# control.net
KiCad netlist of a schematic drawn in EAGLE
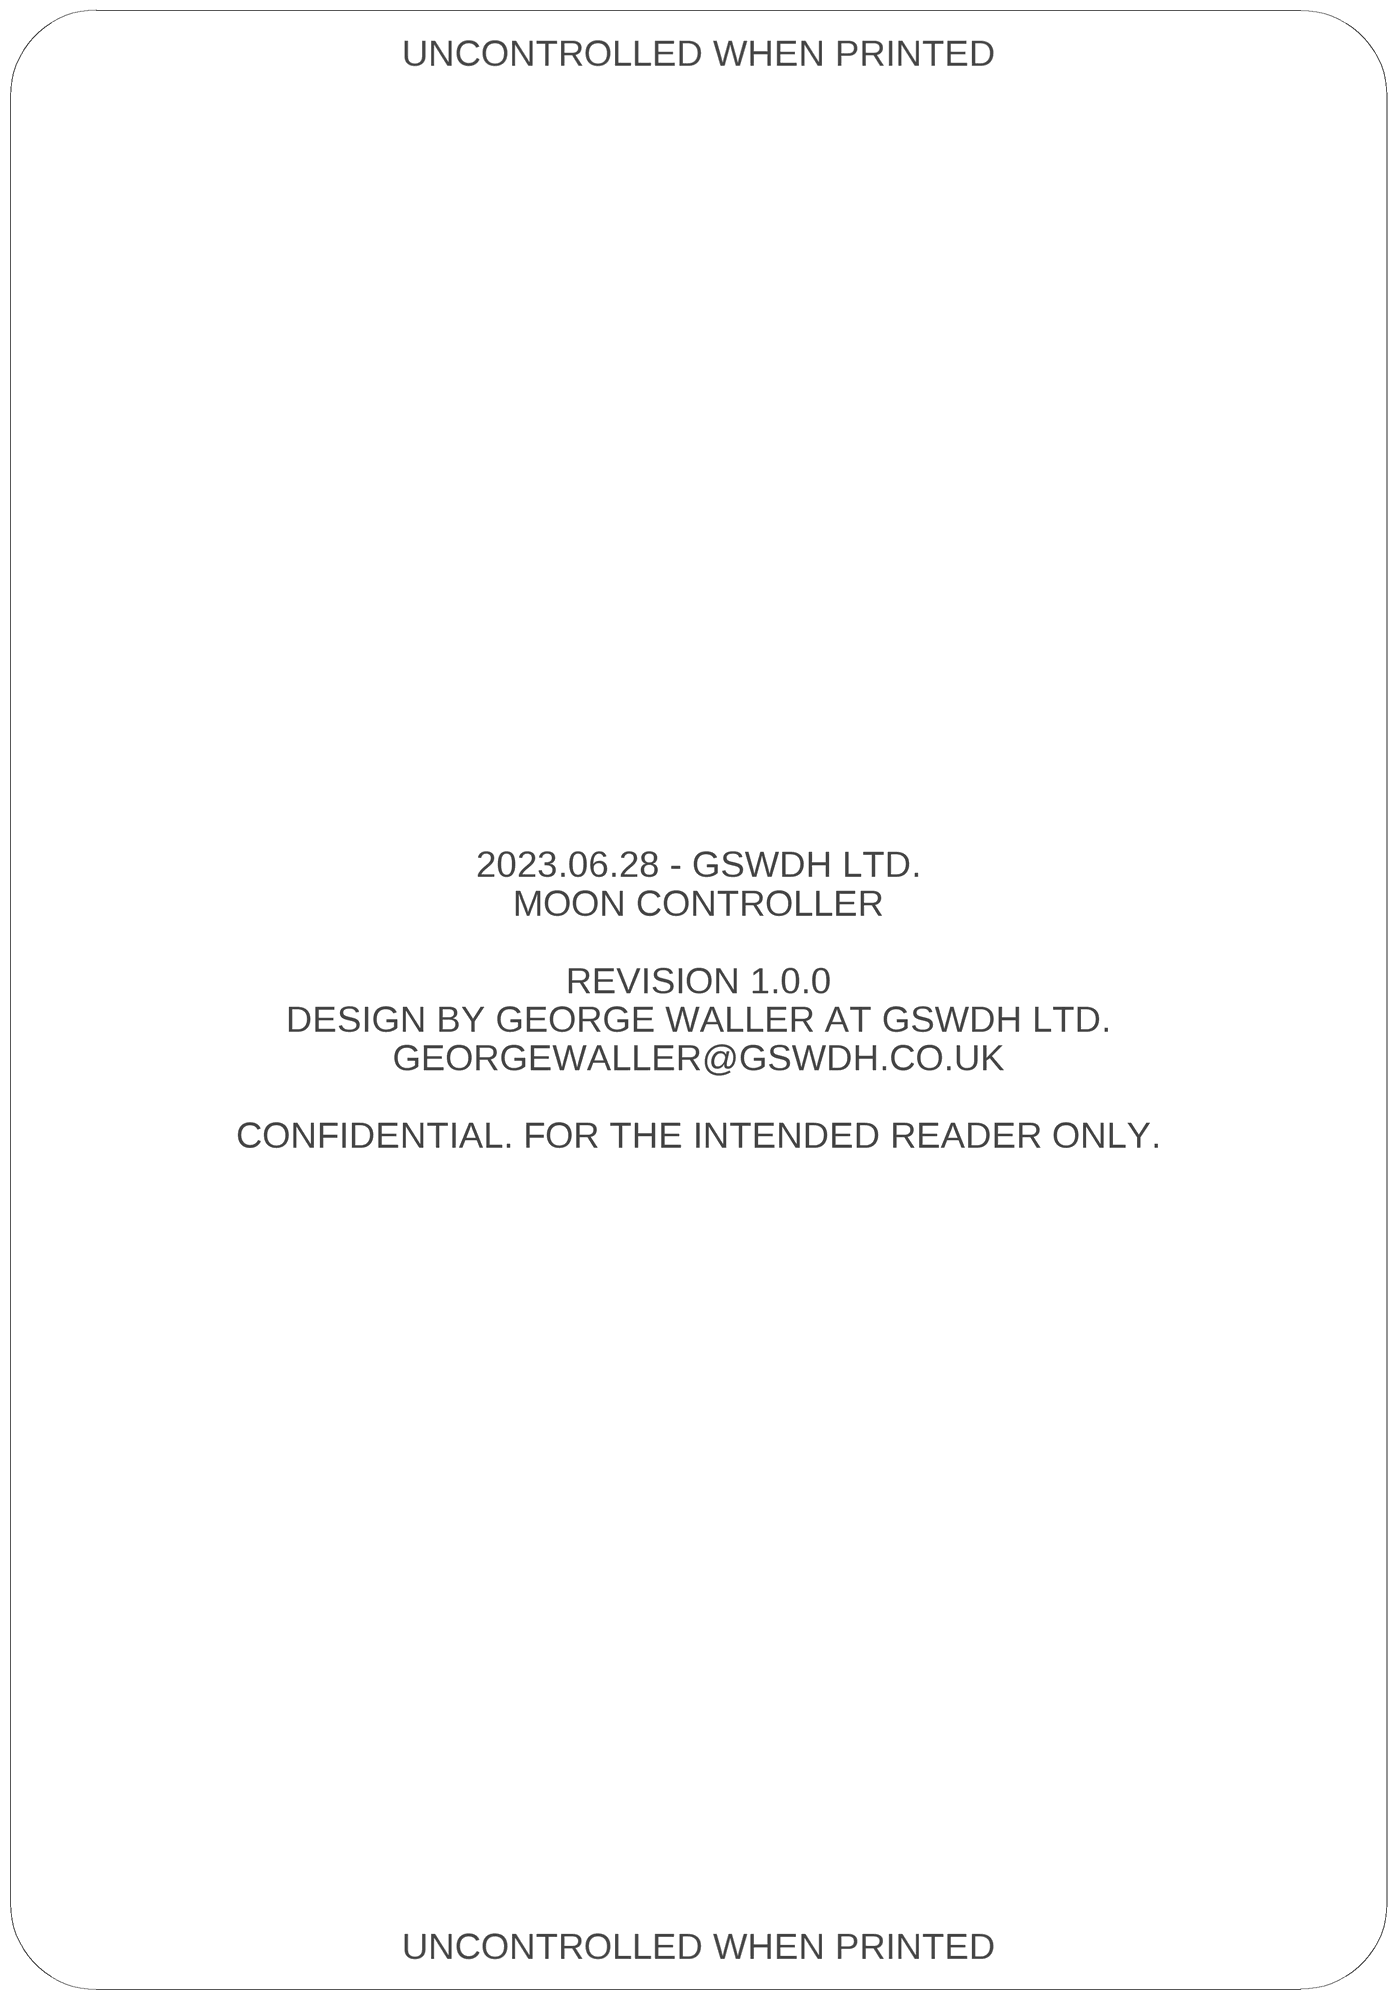
[diagram p0: schematic, sheet 1]
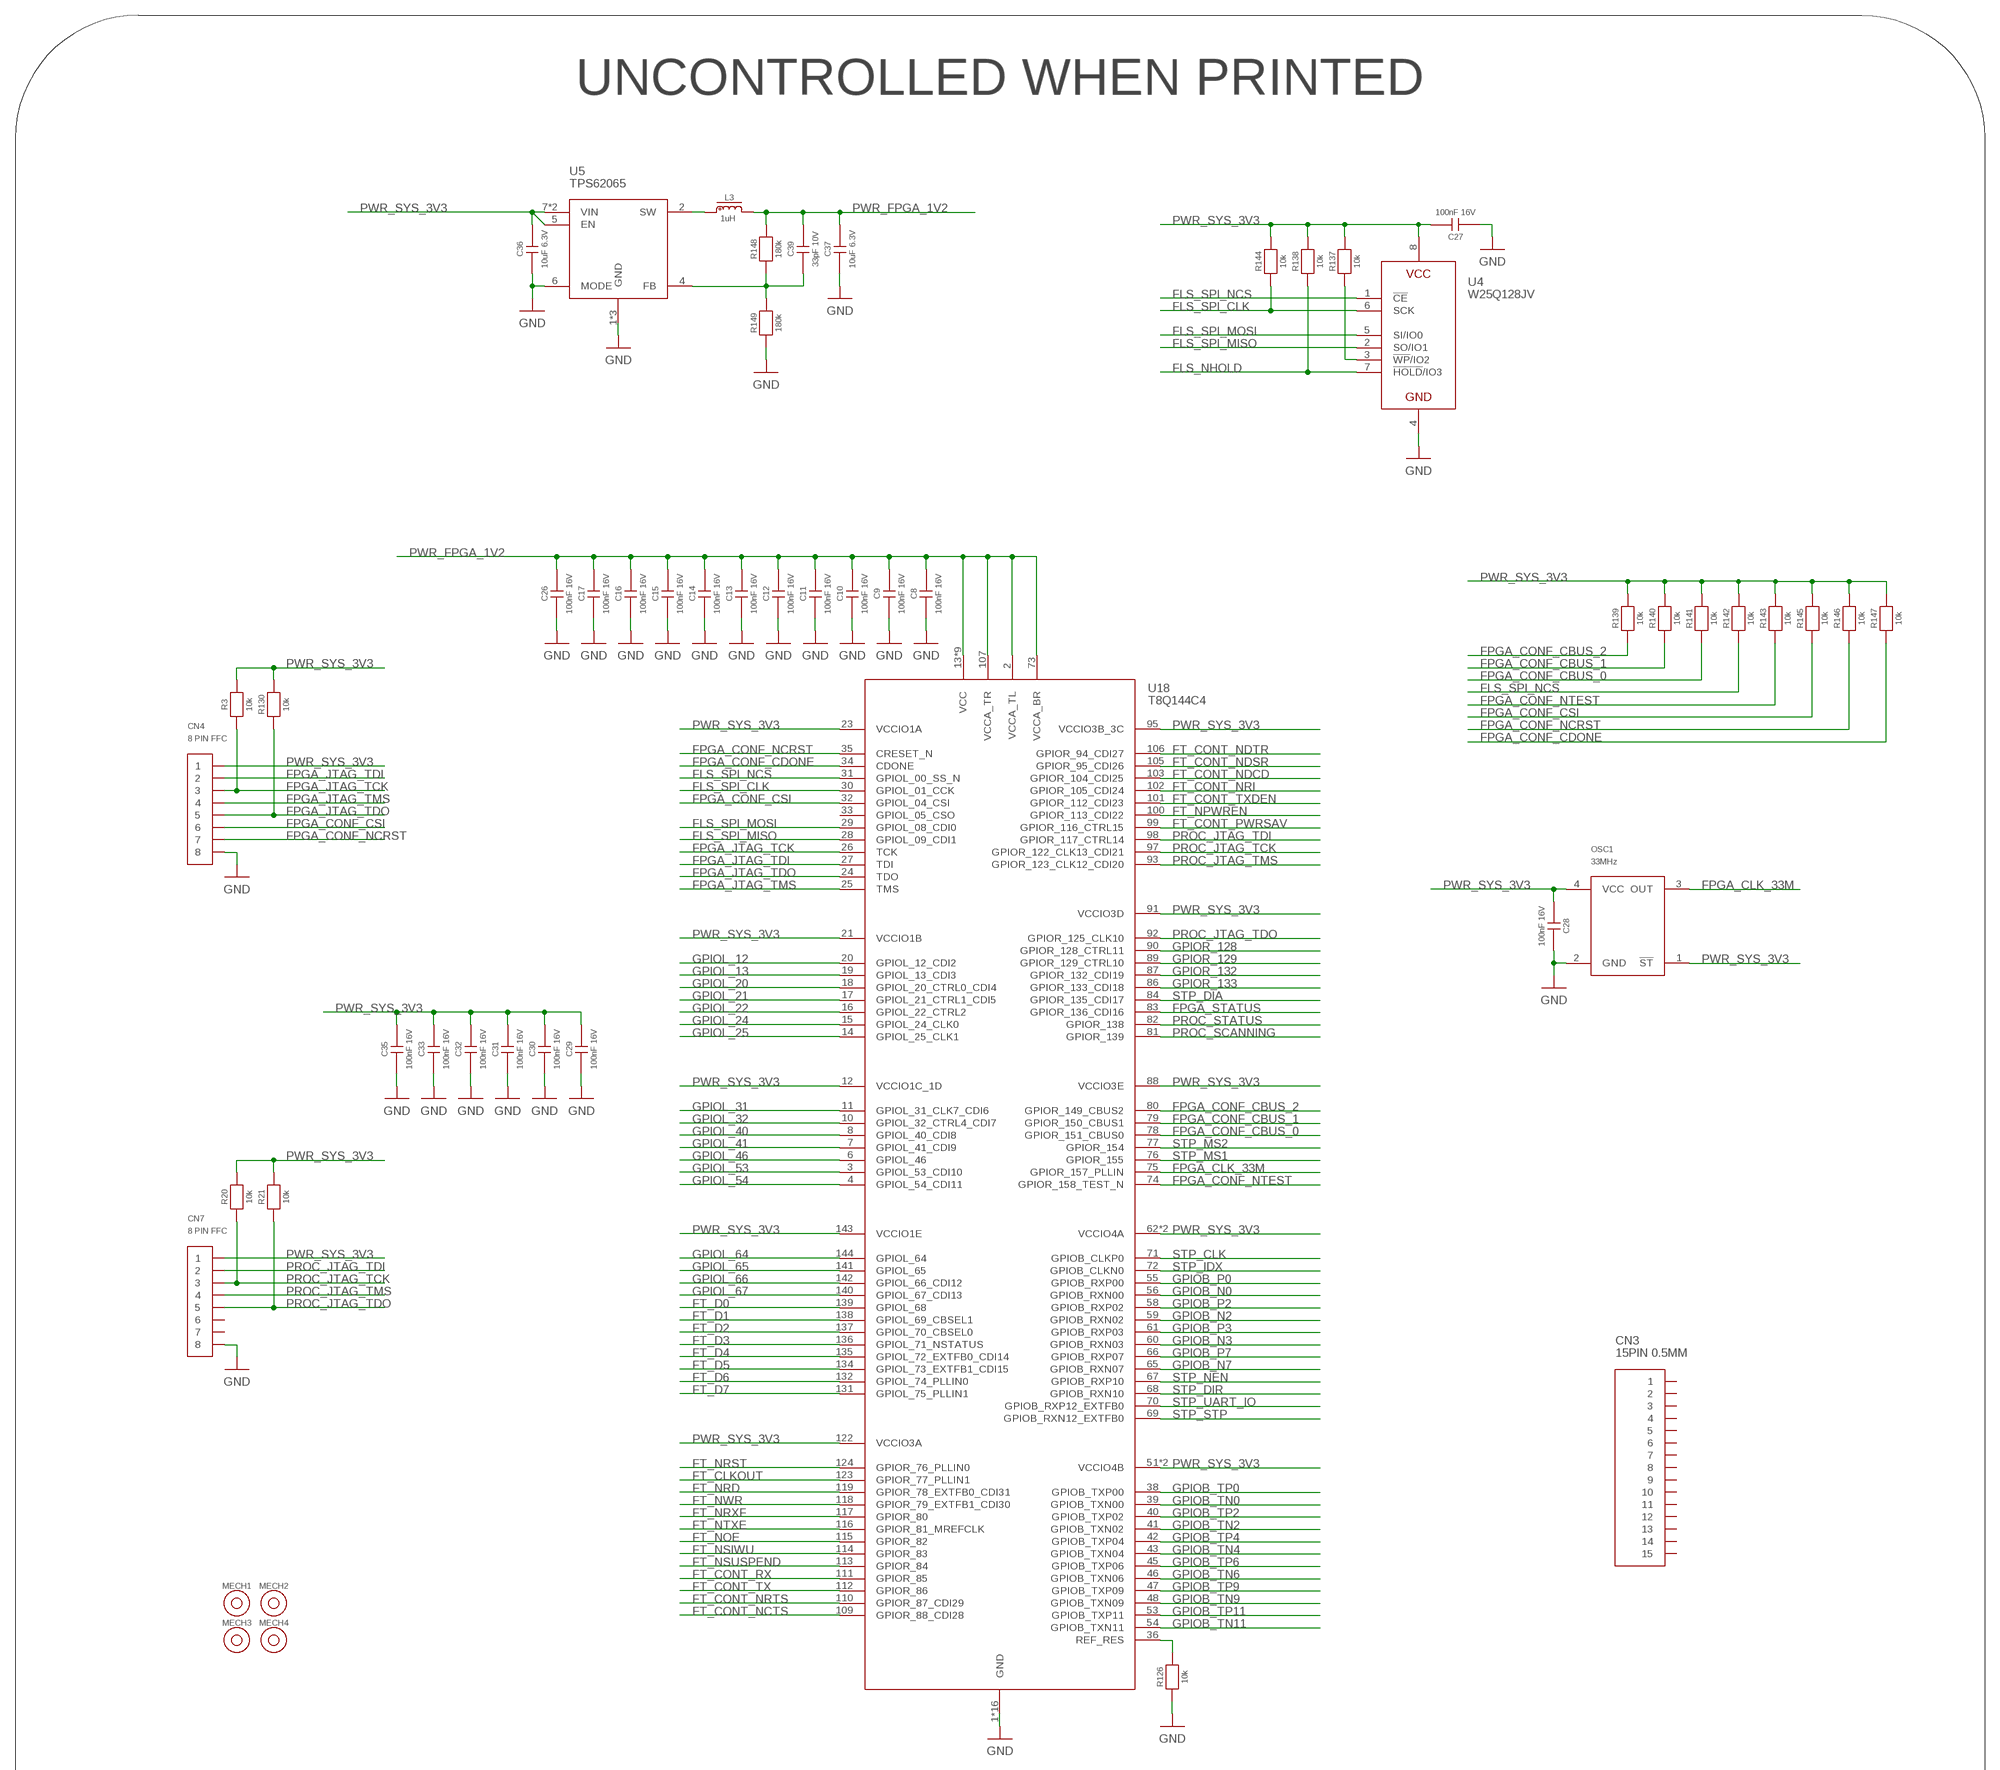
[diagram p1: schematic, sheet 2, part 1 of 2]
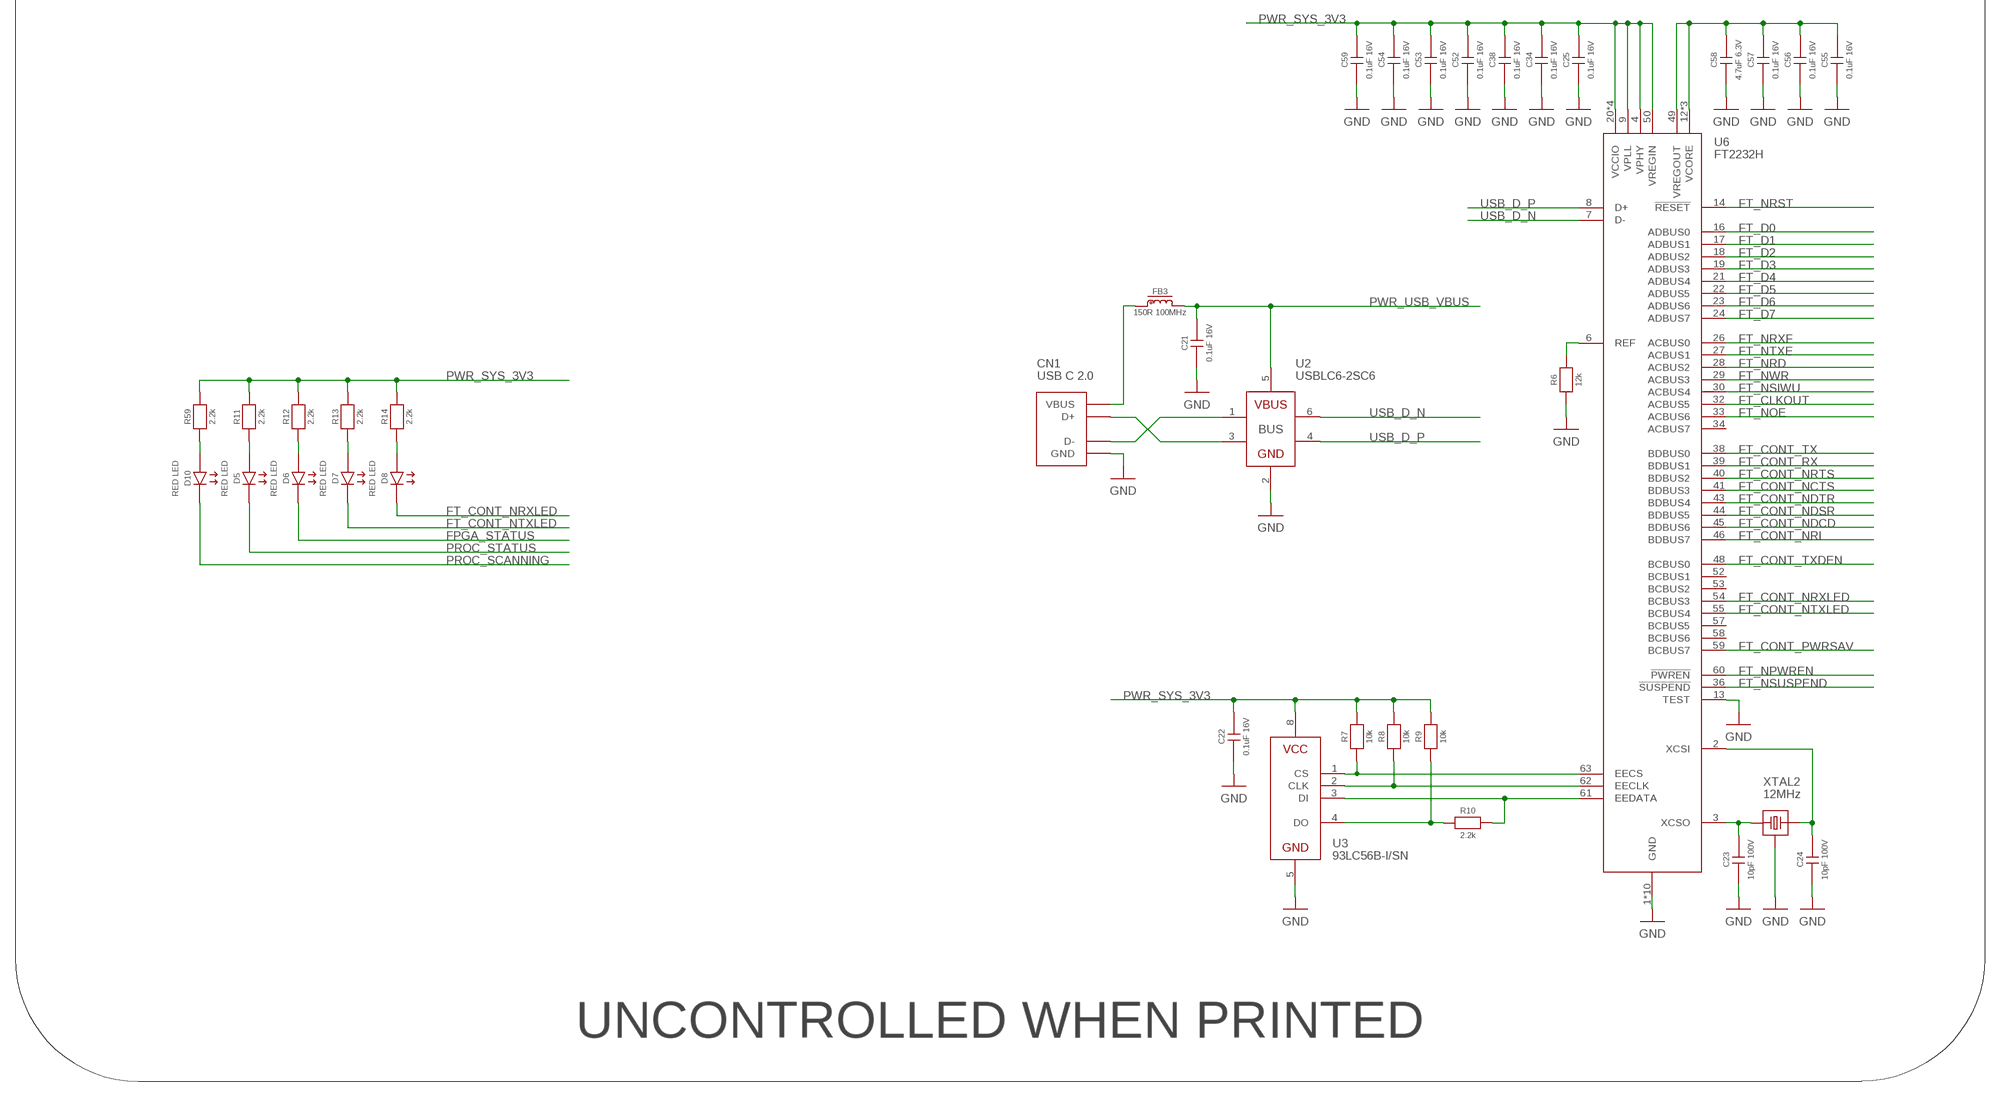
[diagram p2: schematic, sheet 2, part 2 of 2]
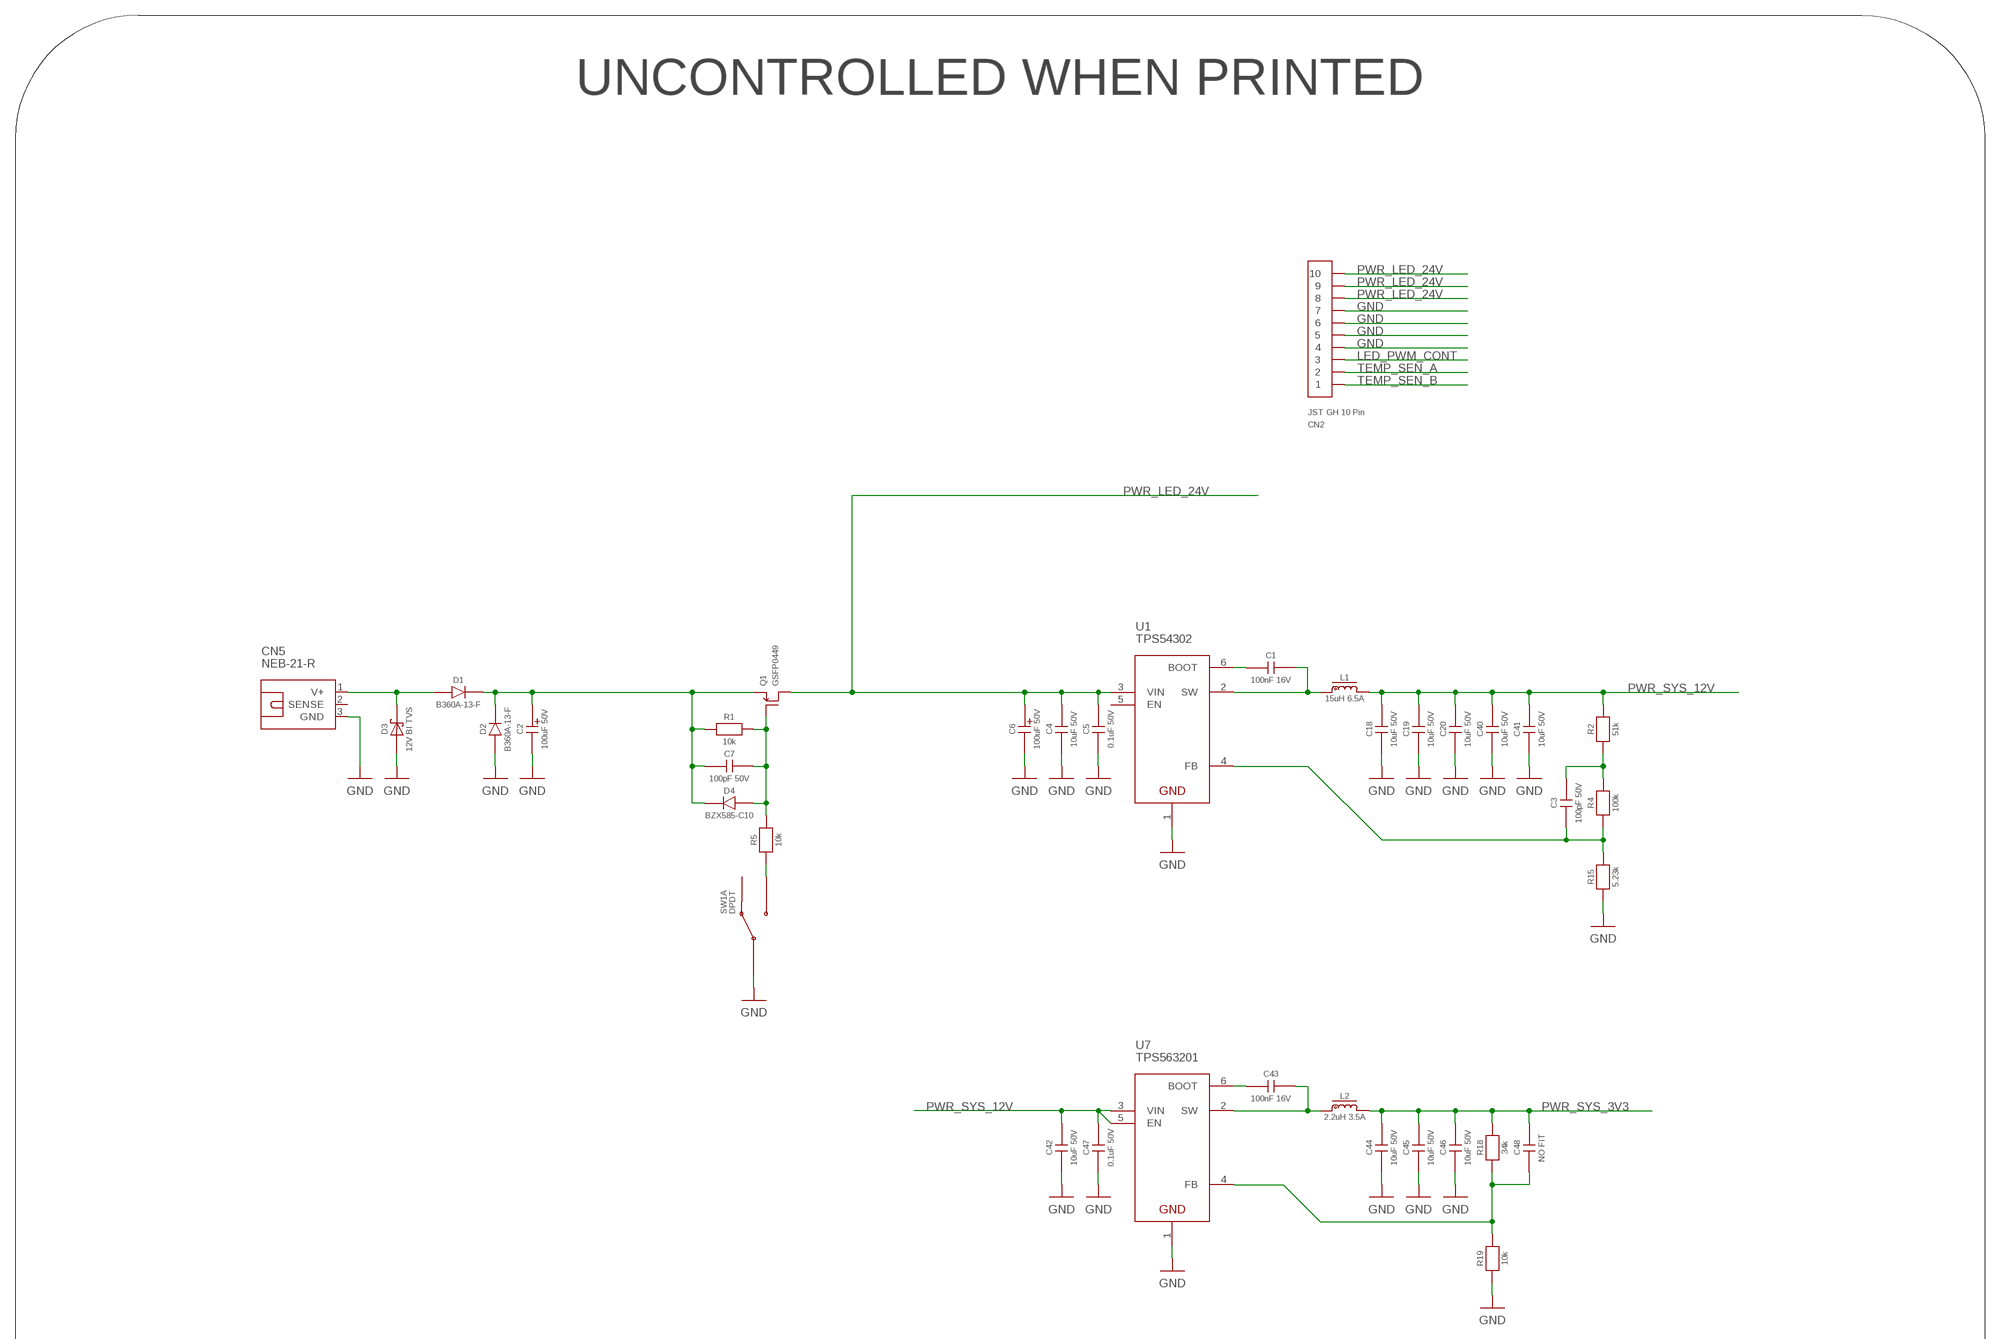
[diagram p3: schematic, sheet 3, part 1 of 2]
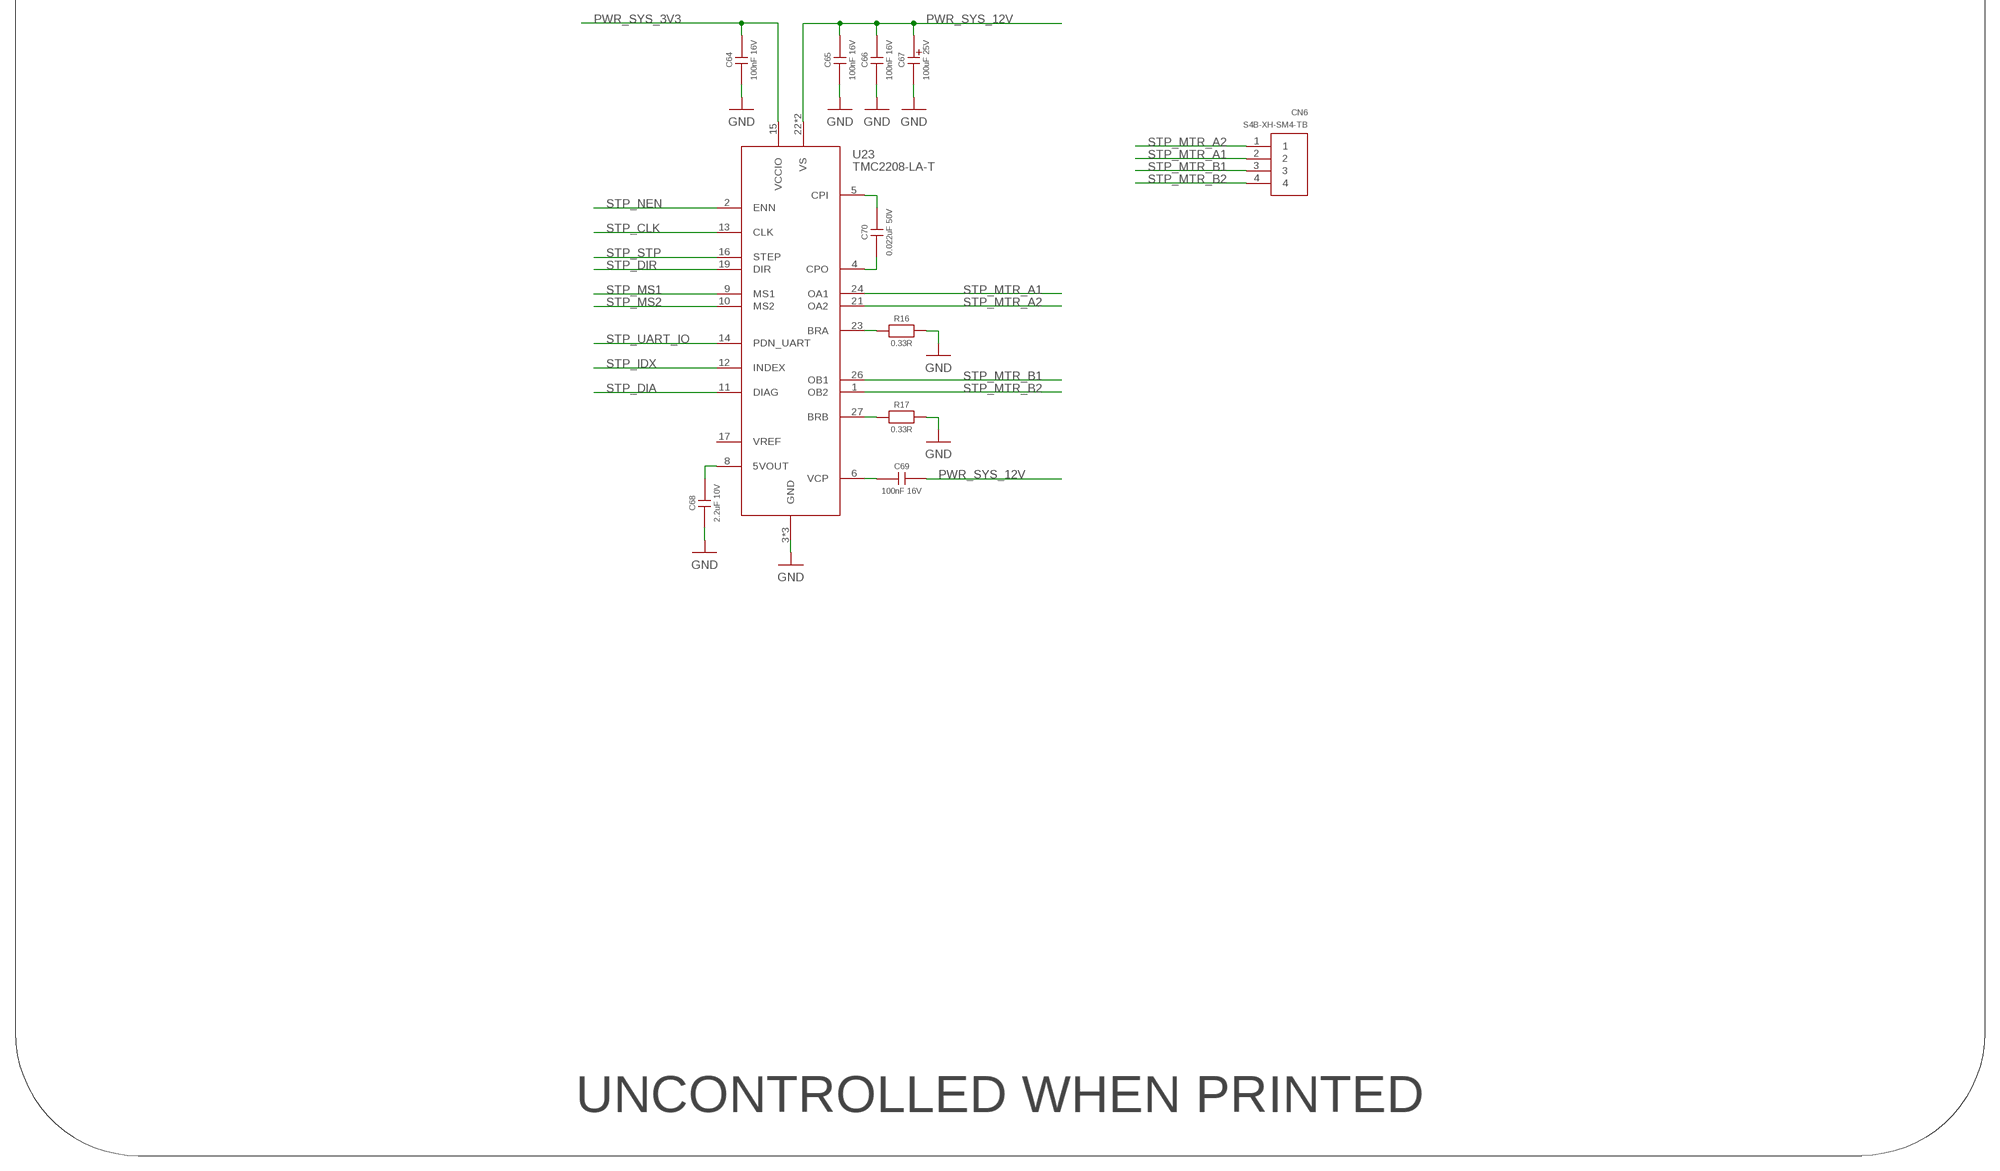
[diagram p4: schematic, sheet 3, part 2 of 2]

(export (version "E")
  (design (tool "Eeschema 10.0.6"))
  (components
    (comp (ref "C8")
      (value "100nF 16V")
      (footprint "eagle-import:0603")
      (libsource (lib "eagle-import") (part "CL10B104KO8WPNC"))
    )
    (comp (ref "C9")
      (value "100nF 16V")
      (footprint "eagle-import:0603")
      (libsource (lib "eagle-import") (part "CL10B104KO8WPNC"))
    )
    (comp (ref "C10")
      (value "100nF 16V")
      (footprint "eagle-import:0603")
      (libsource (lib "eagle-import") (part "CL10B104KO8WPNC"))
    )
    (comp (ref "C11")
      (value "100nF 16V")
      (footprint "eagle-import:0603")
      (libsource (lib "eagle-import") (part "CL10B104KO8WPNC"))
    )
    (comp (ref "C12")
      (value "100nF 16V")
      (footprint "eagle-import:0603")
      (libsource (lib "eagle-import") (part "CL10B104KO8WPNC"))
    )
    (comp (ref "C13")
      (value "100nF 16V")
      (footprint "eagle-import:0603")
      (libsource (lib "eagle-import") (part "CL10B104KO8WPNC"))
    )
    (comp (ref "C14")
      (value "100nF 16V")
      (footprint "eagle-import:0603")
      (libsource (lib "eagle-import") (part "CL10B104KO8WPNC"))
    )
    (comp (ref "C15")
      (value "100nF 16V")
      (footprint "eagle-import:0603")
      (libsource (lib "eagle-import") (part "CL10B104KO8WPNC"))
    )
    (comp (ref "C16")
      (value "100nF 16V")
      (footprint "eagle-import:0603")
      (libsource (lib "eagle-import") (part "CL10B104KO8WPNC"))
    )
    (comp (ref "C17")
      (value "100nF 16V")
      (footprint "eagle-import:0603")
      (libsource (lib "eagle-import") (part "CL10B104KO8WPNC"))
    )
    (comp (ref "C21")
      (value "0.1uF 16V")
      (footprint "eagle-import:0603")
      (fields
        (field (name "MANUFACTURER") "AVX Corporation")
        (field (name "TOLERANCE") "±5%")
        (field (name "VOLTAGE") "16V")
      )
      (libsource (lib "eagle-import") (part "0603YC104JAZ2A"))
    )
    (comp (ref "C22")
      (value "0.1uF 16V")
      (footprint "eagle-import:0603")
      (fields
        (field (name "MANUFACTURER") "AVX Corporation")
        (field (name "TOLERANCE") "±5%")
        (field (name "VOLTAGE") "16V")
      )
      (libsource (lib "eagle-import") (part "0603YC104JAZ2A"))
    )
    (comp (ref "C23")
      (value "10pF 100V")
      (footprint "eagle-import:0603")
      (fields
        (field (name "MANUFACTURER") "AVX Corporation")
        (field (name "TOLERANCE") "±0.1pF")
        (field (name "VOLTAGE") "100V")
      )
      (libsource (lib "eagle-import") (part "06031A100B4T2A"))
    )
    (comp (ref "C24")
      (value "10pF 100V")
      (footprint "eagle-import:0603")
      (fields
        (field (name "MANUFACTURER") "AVX Corporation")
        (field (name "TOLERANCE") "±0.1pF")
        (field (name "VOLTAGE") "100V")
      )
      (libsource (lib "eagle-import") (part "06031A100B4T2A"))
    )
    (comp (ref "C25")
      (value "0.1uF 16V")
      (footprint "eagle-import:0603")
      (fields
        (field (name "MANUFACTURER") "AVX Corporation")
        (field (name "TOLERANCE") "±5%")
        (field (name "VOLTAGE") "16V")
      )
      (libsource (lib "eagle-import") (part "0603YC104JAZ2A"))
    )
    (comp (ref "C26")
      (value "100nF 16V")
      (footprint "eagle-import:0603")
      (libsource (lib "eagle-import") (part "CL10B104KO8WPNC"))
    )
    (comp (ref "C27")
      (value "100nF 16V")
      (footprint "eagle-import:0603")
      (libsource (lib "eagle-import") (part "CL10B104KO8WPNC"))
    )
    (comp (ref "C28")
      (value "100nF 16V")
      (footprint "eagle-import:0603")
      (libsource (lib "eagle-import") (part "CL10B104KO8WPNC"))
    )
    (comp (ref "C29")
      (value "100nF 16V")
      (footprint "eagle-import:0603")
      (libsource (lib "eagle-import") (part "CL10B104KO8WPNC"))
    )
    (comp (ref "C30")
      (value "100nF 16V")
      (footprint "eagle-import:0603")
      (libsource (lib "eagle-import") (part "CL10B104KO8WPNC"))
    )
    (comp (ref "C31")
      (value "100nF 16V")
      (footprint "eagle-import:0603")
      (libsource (lib "eagle-import") (part "CL10B104KO8WPNC"))
    )
    (comp (ref "C32")
      (value "100nF 16V")
      (footprint "eagle-import:0603")
      (libsource (lib "eagle-import") (part "CL10B104KO8WPNC"))
    )
    (comp (ref "C33")
      (value "100nF 16V")
      (footprint "eagle-import:0603")
      (libsource (lib "eagle-import") (part "CL10B104KO8WPNC"))
    )
    (comp (ref "C34")
      (value "0.1uF 16V")
      (footprint "eagle-import:0603")
      (fields
        (field (name "MANUFACTURER") "AVX Corporation")
        (field (name "TOLERANCE") "±5%")
        (field (name "VOLTAGE") "16V")
      )
      (libsource (lib "eagle-import") (part "0603YC104JAZ2A"))
    )
    (comp (ref "C35")
      (value "100nF 16V")
      (footprint "eagle-import:0603")
      (libsource (lib "eagle-import") (part "CL10B104KO8WPNC"))
    )
    (comp (ref "C36")
      (value "10uF 6.3V")
      (footprint "eagle-import:0603")
      (fields
        (field (name "MANUFACTURER") "Samsung Electro-Mechanics")
        (field (name "TOLERANCE") "±10%")
        (field (name "VOLTAGE") "6.3V")
      )
      (libsource (lib "eagle-import") (part "CL10A106KQ8NNWC"))
    )
    (comp (ref "C37")
      (value "10uF 6.3V")
      (footprint "eagle-import:0603")
      (fields
        (field (name "MANUFACTURER") "Samsung Electro-Mechanics")
        (field (name "TOLERANCE") "±10%")
        (field (name "VOLTAGE") "6.3V")
      )
      (libsource (lib "eagle-import") (part "CL10A106KQ8NNWC"))
    )
    (comp (ref "C38")
      (value "0.1uF 16V")
      (footprint "eagle-import:0603")
      (fields
        (field (name "MANUFACTURER") "AVX Corporation")
        (field (name "TOLERANCE") "±5%")
        (field (name "VOLTAGE") "16V")
      )
      (libsource (lib "eagle-import") (part "0603YC104JAZ2A"))
    )
    (comp (ref "C39")
      (value "33pF 10V")
      (footprint "eagle-import:0603")
      (fields
        (field (name "MANUFACTURER") "KEMET")
        (field (name "TOLERANCE") "±5%")
        (field (name "VOLTAGE") "10V")
      )
      (libsource (lib "eagle-import") (part "C0603C330J8GAC7867"))
    )
    (comp (ref "C52")
      (value "0.1uF 16V")
      (footprint "eagle-import:0603")
      (fields
        (field (name "MANUFACTURER") "AVX Corporation")
        (field (name "TOLERANCE") "±5%")
        (field (name "VOLTAGE") "16V")
      )
      (libsource (lib "eagle-import") (part "0603YC104JAZ2A"))
    )
    (comp (ref "C53")
      (value "0.1uF 16V")
      (footprint "eagle-import:0603")
      (fields
        (field (name "MANUFACTURER") "AVX Corporation")
        (field (name "TOLERANCE") "±5%")
        (field (name "VOLTAGE") "16V")
      )
      (libsource (lib "eagle-import") (part "0603YC104JAZ2A"))
    )
    (comp (ref "C54")
      (value "0.1uF 16V")
      (footprint "eagle-import:0603")
      (fields
        (field (name "MANUFACTURER") "AVX Corporation")
        (field (name "TOLERANCE") "±5%")
        (field (name "VOLTAGE") "16V")
      )
      (libsource (lib "eagle-import") (part "0603YC104JAZ2A"))
    )
    (comp (ref "C55")
      (value "0.1uF 16V")
      (footprint "eagle-import:0603")
      (fields
        (field (name "MANUFACTURER") "AVX Corporation")
        (field (name "TOLERANCE") "±5%")
        (field (name "VOLTAGE") "16V")
      )
      (libsource (lib "eagle-import") (part "0603YC104JAZ2A"))
    )
    (comp (ref "C56")
      (value "0.1uF 16V")
      (footprint "eagle-import:0603")
      (fields
        (field (name "MANUFACTURER") "AVX Corporation")
        (field (name "TOLERANCE") "±5%")
        (field (name "VOLTAGE") "16V")
      )
      (libsource (lib "eagle-import") (part "0603YC104JAZ2A"))
    )
    (comp (ref "C57")
      (value "0.1uF 16V")
      (footprint "eagle-import:0603")
      (fields
        (field (name "MANUFACTURER") "AVX Corporation")
        (field (name "TOLERANCE") "±5%")
        (field (name "VOLTAGE") "16V")
      )
      (libsource (lib "eagle-import") (part "0603YC104JAZ2A"))
    )
    (comp (ref "C58")
      (value "4.7uF 6.3V")
      (footprint "eagle-import:0603")
      (fields
        (field (name "MANUFACTURER") "AVX Corporation")
        (field (name "TOLERANCE") "±10%")
        (field (name "VOLTAGE") "6.3V")
      )
      (libsource (lib "eagle-import") (part "06036D475KAT4A"))
    )
    (comp (ref "C59")
      (value "0.1uF 16V")
      (footprint "eagle-import:0603")
      (fields
        (field (name "MANUFACTURER") "AVX Corporation")
        (field (name "TOLERANCE") "±5%")
        (field (name "VOLTAGE") "16V")
      )
      (libsource (lib "eagle-import") (part "0603YC104JAZ2A"))
    )
    (comp (ref "CN1")
      (value "USB C 2.0")
      (footprint "eagle-import:MC-107D")
      (libsource (lib "eagle-import") (part "MC-107D"))
    )
    (comp (ref "CN3")
      (value "15PIN 0.5MM")
      (footprint "eagle-import:SFV15R-1STE1HLF")
      (libsource (lib "eagle-import") (part "SFV15R-1STE1HLF"))
    )
    (comp (ref "CN4")
      (value "8 PIN FFC")
      (footprint "eagle-import:SFV8R-1STBE1HLF")
      (libsource (lib "eagle-import") (part "SFV8R-1STBE1HLF"))
    )
    (comp (ref "CN7")
      (value "8 PIN FFC")
      (footprint "eagle-import:SFV8R-1STBE1HLF")
      (libsource (lib "eagle-import") (part "SFV8R-1STBE1HLF"))
    )
    (comp (ref "D5")
      (value "RED LED")
      (footprint "eagle-import:0603_POLAR")
      (libsource (lib "eagle-import") (part "150060RS75000"))
    )
    (comp (ref "D6")
      (value "RED LED")
      (footprint "eagle-import:0603_POLAR")
      (libsource (lib "eagle-import") (part "150060RS75000"))
    )
    (comp (ref "D7")
      (value "RED LED")
      (footprint "eagle-import:0603_POLAR")
      (libsource (lib "eagle-import") (part "150060RS75000"))
    )
    (comp (ref "D8")
      (value "RED LED")
      (footprint "eagle-import:0603_POLAR")
      (libsource (lib "eagle-import") (part "150060RS75000"))
    )
    (comp (ref "D10")
      (value "RED LED")
      (footprint "eagle-import:0603_POLAR")
      (libsource (lib "eagle-import") (part "150060RS75000"))
    )
    (comp (ref "FB3")
      (value "150R 100MHz")
      (footprint "eagle-import:1206")
      (libsource (lib "eagle-import") (part "ILB1206ER151V"))
    )
    (comp (ref "L3")
      (value "1uH")
      (footprint "eagle-import:1008")
      (libsource (lib "eagle-import") (part "CIGT252010EH1R0MNE"))
    )
    (comp (ref "MECH1")
      (value "6mm x 3mm")
      (footprint "eagle-import:MOUNTHOLE_6X3")
      (libsource (lib "eagle-import") (part "MOUNTHOLE"))
    )
    (comp (ref "MECH2")
      (value "6mm x 3mm")
      (footprint "eagle-import:MOUNTHOLE_6X3")
      (libsource (lib "eagle-import") (part "MOUNTHOLE"))
    )
    (comp (ref "MECH3")
      (value "6mm x 3mm")
      (footprint "eagle-import:MOUNTHOLE_6X3")
      (libsource (lib "eagle-import") (part "MOUNTHOLE"))
    )
    (comp (ref "MECH4")
      (value "6mm x 3mm")
      (footprint "eagle-import:MOUNTHOLE_6X3")
      (libsource (lib "eagle-import") (part "MOUNTHOLE"))
    )
    (comp (ref "OSC1")
      (value "33MHz")
      (footprint "eagle-import:KC2016Z")
      (libsource (lib "eagle-import") (part "KC2016Z33.0000C15XXK"))
    )
    (comp (ref "R3")
      (value "10k")
      (footprint "eagle-import:0603")
      (libsource (lib "eagle-import") (part "ERJ3EKF1002V"))
    )
    (comp (ref "R6")
      (value "12k")
      (footprint "eagle-import:0603")
      (libsource (lib "eagle-import") (part "CRCW060312K0FKEA"))
    )
    (comp (ref "R7")
      (value "10k")
      (footprint "eagle-import:0603")
      (libsource (lib "eagle-import") (part "ERJ3EKF1002V"))
    )
    (comp (ref "R8")
      (value "10k")
      (footprint "eagle-import:0603")
      (libsource (lib "eagle-import") (part "ERJ3EKF1002V"))
    )
    (comp (ref "R9")
      (value "10k")
      (footprint "eagle-import:0603")
      (libsource (lib "eagle-import") (part "ERJ3EKF1002V"))
    )
    (comp (ref "R10")
      (value "2.2k")
      (footprint "eagle-import:0603")
      (fields
        (field (name "MANUFACTURER") "Vishay Dale")
        (field (name "POWER") "0.1W, 1/10W")
        (field (name "TOLERANCE") "±1%")
      )
      (libsource (lib "eagle-import") (part "CRCW06032K20FKEA"))
    )
    (comp (ref "R11")
      (value "2.2k")
      (footprint "eagle-import:0603")
      (fields
        (field (name "MANUFACTURER") "Vishay Dale")
        (field (name "POWER") "0.1W, 1/10W")
        (field (name "TOLERANCE") "±1%")
      )
      (libsource (lib "eagle-import") (part "CRCW06032K20FKEA"))
    )
    (comp (ref "R12")
      (value "2.2k")
      (footprint "eagle-import:0603")
      (fields
        (field (name "MANUFACTURER") "Vishay Dale")
        (field (name "POWER") "0.1W, 1/10W")
        (field (name "TOLERANCE") "±1%")
      )
      (libsource (lib "eagle-import") (part "CRCW06032K20FKEA"))
    )
    (comp (ref "R13")
      (value "2.2k")
      (footprint "eagle-import:0603")
      (fields
        (field (name "MANUFACTURER") "Vishay Dale")
        (field (name "POWER") "0.1W, 1/10W")
        (field (name "TOLERANCE") "±1%")
      )
      (libsource (lib "eagle-import") (part "CRCW06032K20FKEA"))
    )
    (comp (ref "R14")
      (value "2.2k")
      (footprint "eagle-import:0603")
      (fields
        (field (name "MANUFACTURER") "Vishay Dale")
        (field (name "POWER") "0.1W, 1/10W")
        (field (name "TOLERANCE") "±1%")
      )
      (libsource (lib "eagle-import") (part "CRCW06032K20FKEA"))
    )
    (comp (ref "R20")
      (value "10k")
      (footprint "eagle-import:0603")
      (libsource (lib "eagle-import") (part "ERJ3EKF1002V"))
    )
    (comp (ref "R21")
      (value "10k")
      (footprint "eagle-import:0603")
      (libsource (lib "eagle-import") (part "ERJ3EKF1002V"))
    )
    (comp (ref "R59")
      (value "2.2k")
      (footprint "eagle-import:0603")
      (fields
        (field (name "MANUFACTURER") "Vishay Dale")
        (field (name "POWER") "0.1W, 1/10W")
        (field (name "TOLERANCE") "±1%")
      )
      (libsource (lib "eagle-import") (part "CRCW06032K20FKEA"))
    )
    (comp (ref "R126")
      (value "10k")
      (footprint "eagle-import:0603")
      (libsource (lib "eagle-import") (part "ERJ3EKF1002V"))
    )
    (comp (ref "R130")
      (value "10k")
      (footprint "eagle-import:0603")
      (libsource (lib "eagle-import") (part "ERJ3EKF1002V"))
    )
    (comp (ref "R137")
      (value "10k")
      (footprint "eagle-import:0603")
      (libsource (lib "eagle-import") (part "ERJ3EKF1002V"))
    )
    (comp (ref "R138")
      (value "10k")
      (footprint "eagle-import:0603")
      (libsource (lib "eagle-import") (part "ERJ3EKF1002V"))
    )
    (comp (ref "R139")
      (value "10k")
      (footprint "eagle-import:0603")
      (libsource (lib "eagle-import") (part "ERJ3EKF1002V"))
    )
    (comp (ref "R140")
      (value "10k")
      (footprint "eagle-import:0603")
      (libsource (lib "eagle-import") (part "ERJ3EKF1002V"))
    )
    (comp (ref "R141")
      (value "10k")
      (footprint "eagle-import:0603")
      (libsource (lib "eagle-import") (part "ERJ3EKF1002V"))
    )
    (comp (ref "R142")
      (value "10k")
      (footprint "eagle-import:0603")
      (libsource (lib "eagle-import") (part "ERJ3EKF1002V"))
    )
    (comp (ref "R143")
      (value "10k")
      (footprint "eagle-import:0603")
      (libsource (lib "eagle-import") (part "ERJ3EKF1002V"))
    )
    (comp (ref "R144")
      (value "10k")
      (footprint "eagle-import:0603")
      (libsource (lib "eagle-import") (part "ERJ3EKF1002V"))
    )
    (comp (ref "R145")
      (value "10k")
      (footprint "eagle-import:0603")
      (libsource (lib "eagle-import") (part "ERJ3EKF1002V"))
    )
    (comp (ref "R146")
      (value "10k")
      (footprint "eagle-import:0603")
      (libsource (lib "eagle-import") (part "ERJ3EKF1002V"))
    )
    (comp (ref "R147")
      (value "10k")
      (footprint "eagle-import:0603")
      (libsource (lib "eagle-import") (part "ERJ3EKF1002V"))
    )
    (comp (ref "R148")
      (value "180k")
      (footprint "eagle-import:0603")
      (fields
        (field (name "MANUFACTURER") "Vishay Dale")
        (field (name "POWER") "0.1W, 1/10W")
        (field (name "TOLERANCE") "±1%")
      )
      (libsource (lib "eagle-import") (part "CRCW0603180KFKEA"))
    )
    (comp (ref "R149")
      (value "180k")
      (footprint "eagle-import:0603")
      (fields
        (field (name "MANUFACTURER") "Vishay Dale")
        (field (name "POWER") "0.1W, 1/10W")
        (field (name "TOLERANCE") "±1%")
      )
      (libsource (lib "eagle-import") (part "CRCW0603180KFKEA"))
    )
    (comp (ref "U2")
      (value "USBLC6-2SC6")
      (footprint "eagle-import:SOT23-6")
      (libsource (lib "eagle-import") (part "USBLC6-2SC6"))
    )
    (comp (ref "U3")
      (value "93LC56B-I/SN")
      (footprint "eagle-import:SO8")
      (libsource (lib "eagle-import") (part "93LC56B-I/SN"))
    )
    (comp (ref "U4")
      (value "W25Q128JV")
      (footprint "eagle-import:SO8-208MIL")
      (libsource (lib "eagle-import") (part "W25Q128JVSIQ"))
    )
    (comp (ref "U5")
      (value "TPS62065")
      (footprint "eagle-import:WSON8")
      (libsource (lib "eagle-import") (part "TPS62065DSGR"))
    )
    (comp (ref "U6")
      (value "FT2232H")
      (footprint "eagle-import:QFN64")
      (libsource (lib "eagle-import") (part "FT2232H"))
    )
    (comp (ref "U18")
      (value "T8Q144C4")
      (footprint "eagle-import:QFP144")
      (libsource (lib "eagle-import") (part "T8Q144C4"))
    )
    (comp (ref "XTAL2")
      (value "12MHz")
      (footprint "eagle-import:3.2X3.5SMD")
      (libsource (lib "eagle-import") (part "ABM8-12.000MHZ-B2-T"))
    )
    (comp (ref "C1")
      (value "100nF 16V")
      (footprint "eagle-import:0603")
      (libsource (lib "eagle-import") (part "CL10B104KO8WPNC"))
    )
    (comp (ref "C2")
      (value "100uF 50V")
      (footprint "eagle-import:8MM_RADIAL_3.5MM_PITCH")
      (libsource (lib "eagle-import") (part "107CKR050M"))
    )
    (comp (ref "C3")
      (value "100pF 50V")
      (footprint "eagle-import:0603")
      (fields
        (field (name "MANUFACTURER") "AVX Corporation")
        (field (name "TOLERANCE") "±5%")
        (field (name "VOLTAGE") "50V")
      )
      (libsource (lib "eagle-import") (part "06035A101J4T4A"))
    )
    (comp (ref "C4")
      (value "10uF 50V")
      (footprint "eagle-import:1210")
      (libsource (lib "eagle-import") (part "C3225X7S1H106M250AB"))
    )
    (comp (ref "C5")
      (value "0.1uF 50V")
      (footprint "eagle-import:0603")
      (fields
        (field (name "MANUFACTURER") "AVX Corporation")
        (field (name "TOLERANCE") "±5%")
        (field (name "VOLTAGE") "50V")
      )
      (libsource (lib "eagle-import") (part "06035C104JAT2A"))
    )
    (comp (ref "C6")
      (value "100uF 50V")
      (footprint "eagle-import:8MM_RADIAL_3.5MM_PITCH")
      (libsource (lib "eagle-import") (part "107CKR050M"))
    )
    (comp (ref "C7")
      (value "100pF 50V")
      (footprint "eagle-import:0603")
      (fields
        (field (name "MANUFACTURER") "AVX Corporation")
        (field (name "TOLERANCE") "±5%")
        (field (name "VOLTAGE") "50V")
      )
      (libsource (lib "eagle-import") (part "06035A101J4T4A"))
    )
    (comp (ref "C18")
      (value "10uF 50V")
      (footprint "eagle-import:0805")
      (libsource (lib "eagle-import") (part "CL21A106KAYNNNE"))
    )
    (comp (ref "C19")
      (value "10uF 50V")
      (footprint "eagle-import:0805")
      (libsource (lib "eagle-import") (part "CL21A106KAYNNNE"))
    )
    (comp (ref "C20")
      (value "10uF 50V")
      (footprint "eagle-import:0805")
      (libsource (lib "eagle-import") (part "CL21A106KAYNNNE"))
    )
    (comp (ref "C40")
      (value "10uF 50V")
      (footprint "eagle-import:0805")
      (libsource (lib "eagle-import") (part "CL21A106KAYNNNE"))
    )
    (comp (ref "C41")
      (value "10uF 50V")
      (footprint "eagle-import:0805")
      (libsource (lib "eagle-import") (part "CL21A106KAYNNNE"))
    )
    (comp (ref "C42")
      (value "10uF 50V")
      (footprint "eagle-import:0805")
      (libsource (lib "eagle-import") (part "CL21A106KAYNNNE"))
    )
    (comp (ref "C43")
      (value "100nF 16V")
      (footprint "eagle-import:0603")
      (libsource (lib "eagle-import") (part "CL10B104KO8WPNC"))
    )
    (comp (ref "C44")
      (value "10uF 50V")
      (footprint "eagle-import:0805")
      (libsource (lib "eagle-import") (part "CL21A106KAYNNNE"))
    )
    (comp (ref "C45")
      (value "10uF 50V")
      (footprint "eagle-import:0805")
      (libsource (lib "eagle-import") (part "CL21A106KAYNNNE"))
    )
    (comp (ref "C46")
      (value "10uF 50V")
      (footprint "eagle-import:0805")
      (libsource (lib "eagle-import") (part "CL21A106KAYNNNE"))
    )
    (comp (ref "C47")
      (value "0.1uF 50V")
      (footprint "eagle-import:0603")
      (fields
        (field (name "MANUFACTURER") "AVX Corporation")
        (field (name "TOLERANCE") "±5%")
        (field (name "VOLTAGE") "50V")
      )
      (libsource (lib "eagle-import") (part "06035C104JAT2A"))
    )
    (comp (ref "C48")
      (value "NO FIT")
      (footprint "eagle-import:0603")
      (fields
        (field (name "MANUFACTURER") "AVX Corporation")
        (field (name "TOLERANCE") "±5%")
        (field (name "VOLTAGE") "50V")
      )
      (libsource (lib "eagle-import") (part "06035A101J4T4A"))
    )
    (comp (ref "C64")
      (value "100nF 16V")
      (footprint "eagle-import:0603")
      (libsource (lib "eagle-import") (part "CL10B104KO8WPNC"))
    )
    (comp (ref "C65")
      (value "100nF 16V")
      (footprint "eagle-import:0603")
      (libsource (lib "eagle-import") (part "CL10B104KO8WPNC"))
    )
    (comp (ref "C66")
      (value "100nF 16V")
      (footprint "eagle-import:0603")
      (libsource (lib "eagle-import") (part "CL10B104KO8WPNC"))
    )
    (comp (ref "C67")
      (value "100uF 25V")
      (footprint "eagle-import:5MM_RADIAL_2MM_PITCH")
      (libsource (lib "eagle-import") (part "UVY1E101MDD"))
    )
    (comp (ref "C68")
      (value "2.2uF 10V")
      (footprint "eagle-import:0603")
      (fields
        (field (name "MANUFACTURER") "AVX Corporation")
        (field (name "TOLERANCE") "±10%")
        (field (name "VOLTAGE") "10V")
      )
      (libsource (lib "eagle-import") (part "0603ZC225KAT2A"))
    )
    (comp (ref "C69")
      (value "100nF 16V")
      (footprint "eagle-import:0603")
      (libsource (lib "eagle-import") (part "CL10B104KO8WPNC"))
    )
    (comp (ref "C70")
      (value "0.022uF 50V")
      (footprint "eagle-import:0603")
      (fields
        (field (name "MANUFACTURER") "KEMET")
        (field (name "TOLERANCE") "±10%")
        (field (name "VOLTAGE") "50V")
      )
      (libsource (lib "eagle-import") (part "C0603C223K5REC7867"))
    )
    (comp (ref "CN2")
      (value "JST GH 10 Pin")
      (footprint "eagle-import:1.25-10PWT")
      (libsource (lib "eagle-import") (part "1.25-10PWT"))
    )
    (comp (ref "CN5")
      (value "NEB-21-R")
      (footprint "eagle-import:NEB-21-R")
      (libsource (lib "eagle-import") (part "NEB-21-R"))
    )
    (comp (ref "CN6")
      (value "S4B-XH-SM4-TB")
      (footprint "eagle-import:S4B-XH-SM4-TB")
      (libsource (lib "eagle-import") (part "S4B-XH-SM4-TB"))
    )
    (comp (ref "D1")
      (value "B360A-13-F")
      (footprint "eagle-import:DO214AC")
      (libsource (lib "eagle-import") (part "B360A-13-F"))
    )
    (comp (ref "D2")
      (value "B360A-13-F")
      (footprint "eagle-import:DO214AC")
      (libsource (lib "eagle-import") (part "B360A-13-F"))
    )
    (comp (ref "D3")
      (value "12V BI TVS")
      (footprint "eagle-import:DO214AC")
      (libsource (lib "eagle-import") (part "SMBJ12CA-13-F"))
    )
    (comp (ref "D4")
      (value "BZX585-C10")
      (footprint "eagle-import:SOD_523")
      (libsource (lib "eagle-import") (part "BZT52C10T-7"))
    )
    (comp (ref "L1")
      (value "15uH 6.5A")
      (footprint "eagle-import:SRP1035A")
      (libsource (lib "eagle-import") (part "MWSA1004S-150MT"))
    )
    (comp (ref "L2")
      (value "2.2uH 3.5A")
      (footprint "eagle-import:SRN5040")
      (libsource (lib "eagle-import") (part "SRN5040-2R2Y"))
    )
    (comp (ref "Q1")
      (value "GSFP0449")
      (footprint "eagle-import:SO8_POWERPAK")
      (libsource (lib "eagle-import") (part "GSFP0449"))
    )
    (comp (ref "R1")
      (value "10k")
      (footprint "eagle-import:0603")
      (fields
        (field (name "MANUFACTURER") "Vishay Dale")
        (field (name "POWER") "0.1W, 1/10W")
        (field (name "TOLERANCE") "±1%")
      )
      (libsource (lib "eagle-import") (part "CRCW060310K0FKTA"))
    )
    (comp (ref "R2")
      (value "51k")
      (footprint "eagle-import:0603")
      (libsource (lib "eagle-import") (part "CRCW060351K0FKEA"))
    )
    (comp (ref "R4")
      (value "100k")
      (footprint "eagle-import:0603")
      (fields
        (field (name "MANUFACTURER") "Vishay Dale")
        (field (name "POWER") "0.1W, 1/10W")
        (field (name "TOLERANCE") "±1%")
      )
      (libsource (lib "eagle-import") (part "CRCW0603100KFKEB"))
    )
    (comp (ref "R5")
      (value "10k")
      (footprint "eagle-import:0603")
      (fields
        (field (name "MANUFACTURER") "Vishay Dale")
        (field (name "POWER") "0.1W, 1/10W")
        (field (name "TOLERANCE") "±1%")
      )
      (libsource (lib "eagle-import") (part "CRCW060310K0FKTA"))
    )
    (comp (ref "R15")
      (value "5.23k")
      (footprint "eagle-import:0603")
      (fields
        (field (name "MANUFACTURER") "Vishay Dale")
        (field (name "POWER") "0.1W, 1/10W")
        (field (name "TOLERANCE") "±1%")
      )
      (libsource (lib "eagle-import") (part "CRCW06035K23FKEA"))
    )
    (comp (ref "R16")
      (value "0.33R")
      (footprint "eagle-import:0603")
      (libsource (lib "eagle-import") (part "CRL0603-FW-R330ELF"))
    )
    (comp (ref "R17")
      (value "0.33R")
      (footprint "eagle-import:0603")
      (libsource (lib "eagle-import") (part "CRL0603-FW-R330ELF"))
    )
    (comp (ref "R18")
      (value "34k")
      (footprint "eagle-import:0603")
      (fields
        (field (name "MANUFACTURER") "Vishay Dale")
        (field (name "POWER") "0.1W, 1/10W")
        (field (name "TOLERANCE") "±1%")
      )
      (libsource (lib "eagle-import") (part "CRCW060334K0FKEA"))
    )
    (comp (ref "R19")
      (value "10k")
      (footprint "eagle-import:0603")
      (fields
        (field (name "MANUFACTURER") "Vishay Dale")
        (field (name "POWER") "0.1W, 1/10W")
        (field (name "TOLERANCE") "±1%")
      )
      (libsource (lib "eagle-import") (part "CRCW060310K0FKTA"))
    )
    (comp (ref "SW1")
      (value "DPDT")
      (footprint "eagle-import:PBH2UEESNPNAGX")
      (libsource (lib "eagle-import") (part "PBH2UEESNPNAGX"))
    )
    (comp (ref "U1")
      (value "TPS54302")
      (footprint "eagle-import:SOT23-6")
      (libsource (lib "eagle-import") (part "TPS54302"))
    )
    (comp (ref "U7")
      (value "TPS563201")
      (footprint "eagle-import:SOT23-6")
      (libsource (lib "eagle-import") (part "TPS563201DDCR"))
    )
    (comp (ref "U23")
      (value "TMC2208-LA-T")
      (footprint "eagle-import:QFN28")
      (libsource (lib "eagle-import") (part "TMC2208-LA-T"))
    )
  )
  (nets
    (net (code "1") (name "FLS_NHOLD") (class "Default")
      (node (ref "R138") (pin "1") (pinfunction "1_1") (pintype "bidirectional"))
      (node (ref "U4") (pin "7") (pinfunction "~{HOLD}/IO3_7") (pintype "bidirectional"))
    )
    (net (code "2") (name "FLS_SPI_CLK") (class "Default")
      (node (ref "R144") (pin "1") (pinfunction "1_1") (pintype "bidirectional"))
      (node (ref "U18") (pin "30") (pinfunction "GPIOL_01_CCK_30") (pintype "bidirectional"))
      (node (ref "U4") (pin "6") (pinfunction "SCK_6") (pintype "bidirectional"))
    )
    (net (code "3") (name "FLS_SPI_MISO") (class "Default")
      (node (ref "U18") (pin "28") (pinfunction "GPIOL_09_CDI1_28") (pintype "bidirectional"))
      (node (ref "U4") (pin "2") (pinfunction "SO/IO1_2") (pintype "bidirectional"))
    )
    (net (code "4") (name "FLS_SPI_MOSI") (class "Default")
      (node (ref "U18") (pin "29") (pinfunction "GPIOL_08_CDI0_29") (pintype "bidirectional"))
      (node (ref "U4") (pin "5") (pinfunction "SI/IO0_5") (pintype "bidirectional"))
    )
    (net (code "5") (name "FLS_SPI_NCS") (class "Default")
      (node (ref "R142") (pin "1") (pinfunction "1_1") (pintype "bidirectional"))
      (node (ref "U18") (pin "31") (pinfunction "GPIOL_00_SS_N_31") (pintype "bidirectional"))
      (node (ref "U4") (pin "1") (pinfunction "~{CE}_1") (pintype "bidirectional"))
    )
    (net (code "6") (name "FPGA_CLK_33M") (class "Default")
      (node (ref "OSC1") (pin "3") (pinfunction "OUT_3") (pintype "bidirectional"))
      (node (ref "U18") (pin "75") (pinfunction "GPIOR_157_PLLIN_75") (pintype "bidirectional"))
    )
    (net (code "7") (name "FPGA_CONF_CBUS_0") (class "Default")
      (node (ref "R141") (pin "1") (pinfunction "1_1") (pintype "bidirectional"))
      (node (ref "U18") (pin "78") (pinfunction "GPIOR_151_CBUS0_78") (pintype "bidirectional"))
    )
    (net (code "8") (name "FPGA_CONF_CBUS_1") (class "Default")
      (node (ref "R140") (pin "1") (pinfunction "1_1") (pintype "bidirectional"))
      (node (ref "U18") (pin "79") (pinfunction "GPIOR_150_CBUS1_79") (pintype "bidirectional"))
    )
    (net (code "9") (name "FPGA_CONF_CBUS_2") (class "Default")
      (node (ref "R139") (pin "1") (pinfunction "1_1") (pintype "bidirectional"))
      (node (ref "U18") (pin "80") (pinfunction "GPIOR_149_CBUS2_80") (pintype "bidirectional"))
    )
    (net (code "10") (name "FPGA_CONF_CDONE") (class "Default")
      (node (ref "R147") (pin "1") (pinfunction "1_1") (pintype "bidirectional"))
      (node (ref "U18") (pin "34") (pinfunction "CDONE_34") (pintype "bidirectional"))
    )
    (net (code "11") (name "FPGA_CONF_CSI") (class "Default")
      (node (ref "CN4") (pin "6") (pinfunction "6_6") (pintype "bidirectional"))
      (node (ref "R145") (pin "1") (pinfunction "1_1") (pintype "bidirectional"))
      (node (ref "U18") (pin "32") (pinfunction "GPIOL_04_CSI_32") (pintype "bidirectional"))
    )
    (net (code "12") (name "FPGA_CONF_NCRST") (class "Default")
      (node (ref "CN4") (pin "7") (pinfunction "7_7") (pintype "bidirectional"))
      (node (ref "R146") (pin "1") (pinfunction "1_1") (pintype "bidirectional"))
      (node (ref "U18") (pin "35") (pinfunction "CRESET_N_35") (pintype "bidirectional"))
    )
    (net (code "13") (name "FPGA_CONF_NTEST") (class "Default")
      (node (ref "R143") (pin "1") (pinfunction "1_1") (pintype "bidirectional"))
      (node (ref "U18") (pin "74") (pinfunction "GPIOR_158_TEST_N_74") (pintype "bidirectional"))
    )
    (net (code "14") (name "FPGA_JTAG_TCK") (class "Default")
      (node (ref "CN4") (pin "3") (pinfunction "3_3") (pintype "bidirectional"))
      (node (ref "R3") (pin "1") (pinfunction "1_1") (pintype "bidirectional"))
      (node (ref "U18") (pin "26") (pinfunction "TCK_26") (pintype "bidirectional"))
    )
    (net (code "15") (name "FPGA_JTAG_TDI") (class "Default")
      (node (ref "CN4") (pin "2") (pinfunction "2_2") (pintype "bidirectional"))
      (node (ref "U18") (pin "27") (pinfunction "TDI_27") (pintype "bidirectional"))
    )
    (net (code "16") (name "FPGA_JTAG_TDO") (class "Default")
      (node (ref "CN4") (pin "5") (pinfunction "5_5") (pintype "bidirectional"))
      (node (ref "R130") (pin "1") (pinfunction "1_1") (pintype "bidirectional"))
      (node (ref "U18") (pin "24") (pinfunction "TDO_24") (pintype "bidirectional"))
    )
    (net (code "17") (name "FPGA_JTAG_TMS") (class "Default")
      (node (ref "CN4") (pin "4") (pinfunction "4_4") (pintype "bidirectional"))
      (node (ref "U18") (pin "25") (pinfunction "TMS_25") (pintype "bidirectional"))
    )
    (net (code "18") (name "FPGA_STATUS") (class "Default")
      (node (ref "D6") (pin "K") (pinfunction "K_K") (pintype "bidirectional"))
      (node (ref "U18") (pin "83") (pinfunction "GPIOR_136_CDI16_83") (pintype "bidirectional"))
    )
    (net (code "19") (name "FT_CLKOUT") (class "Default")
      (node (ref "U18") (pin "123") (pinfunction "GPIOR_77_PLLIN1_123") (pintype "bidirectional"))
      (node (ref "U6") (pin "32") (pinfunction "ACBUS5_32") (pintype "bidirectional"))
    )
    (net (code "20") (name "FT_CONT_NCTS") (class "Default")
      (node (ref "U18") (pin "109") (pinfunction "GPIOR_88_CDI28_109") (pintype "bidirectional"))
      (node (ref "U6") (pin "41") (pinfunction "BDBUS3_41") (pintype "bidirectional"))
    )
    (net (code "21") (name "FT_CONT_NDCD") (class "Default")
      (node (ref "U18") (pin "103") (pinfunction "GPIOR_104_CDI25_103") (pintype "bidirectional"))
      (node (ref "U6") (pin "45") (pinfunction "BDBUS6_45") (pintype "bidirectional"))
    )
    (net (code "22") (name "FT_CONT_NDSR") (class "Default")
      (node (ref "U18") (pin "105") (pinfunction "GPIOR_95_CDI26_105") (pintype "bidirectional"))
      (node (ref "U6") (pin "44") (pinfunction "BDBUS5_44") (pintype "bidirectional"))
    )
    (net (code "23") (name "FT_CONT_NDTR") (class "Default")
      (node (ref "U18") (pin "106") (pinfunction "GPIOR_94_CDI27_106") (pintype "bidirectional"))
      (node (ref "U6") (pin "43") (pinfunction "BDBUS4_43") (pintype "bidirectional"))
    )
    (net (code "24") (name "FT_CONT_NRI") (class "Default")
      (node (ref "U18") (pin "102") (pinfunction "GPIOR_105_CDI24_102") (pintype "bidirectional"))
      (node (ref "U6") (pin "46") (pinfunction "BDBUS7_46") (pintype "bidirectional"))
    )
    (net (code "25") (name "FT_CONT_NRTS") (class "Default")
      (node (ref "U18") (pin "110") (pinfunction "GPIOR_87_CDI29_110") (pintype "bidirectional"))
      (node (ref "U6") (pin "40") (pinfunction "BDBUS2_40") (pintype "bidirectional"))
    )
    (net (code "26") (name "FT_CONT_NRXLED") (class "Default")
      (node (ref "D8") (pin "K") (pinfunction "K_K") (pintype "bidirectional"))
      (node (ref "U6") (pin "54") (pinfunction "BCBUS3_54") (pintype "bidirectional"))
    )
    (net (code "27") (name "FT_CONT_NTXLED") (class "Default")
      (node (ref "D7") (pin "K") (pinfunction "K_K") (pintype "bidirectional"))
      (node (ref "U6") (pin "55") (pinfunction "BCBUS4_55") (pintype "bidirectional"))
    )
    (net (code "28") (name "FT_CONT_PWRSAV") (class "Default")
      (node (ref "U18") (pin "99") (pinfunction "GPIOR_116_CTRL15_99") (pintype "bidirectional"))
      (node (ref "U6") (pin "59") (pinfunction "BCBUS7_59") (pintype "bidirectional"))
    )
    (net (code "29") (name "FT_CONT_RX") (class "Default")
      (node (ref "U18") (pin "111") (pinfunction "GPIOR_85_111") (pintype "bidirectional"))
      (node (ref "U6") (pin "39") (pinfunction "BDBUS1_39") (pintype "bidirectional"))
    )
    (net (code "30") (name "FT_CONT_TX") (class "Default")
      (node (ref "U18") (pin "112") (pinfunction "GPIOR_86_112") (pintype "bidirectional"))
      (node (ref "U6") (pin "38") (pinfunction "BDBUS0_38") (pintype "bidirectional"))
    )
    (net (code "31") (name "FT_CONT_TXDEN") (class "Default")
      (node (ref "U18") (pin "101") (pinfunction "GPIOR_112_CDI23_101") (pintype "bidirectional"))
      (node (ref "U6") (pin "48") (pinfunction "BCBUS0_48") (pintype "bidirectional"))
    )
    (net (code "32") (name "FT_D0") (class "Default")
      (node (ref "U18") (pin "139") (pinfunction "GPIOL_68_139") (pintype "bidirectional"))
      (node (ref "U6") (pin "16") (pinfunction "ADBUS0_16") (pintype "bidirectional"))
    )
    (net (code "33") (name "FT_D1") (class "Default")
      (node (ref "U18") (pin "138") (pinfunction "GPIOL_69_CBSEL1_138") (pintype "bidirectional"))
      (node (ref "U6") (pin "17") (pinfunction "ADBUS1_17") (pintype "bidirectional"))
    )
    (net (code "34") (name "FT_D2") (class "Default")
      (node (ref "U18") (pin "137") (pinfunction "GPIOL_70_CBSEL0_137") (pintype "bidirectional"))
      (node (ref "U6") (pin "18") (pinfunction "ADBUS2_18") (pintype "bidirectional"))
    )
    (net (code "35") (name "FT_D3") (class "Default")
      (node (ref "U18") (pin "136") (pinfunction "GPIOL_71_NSTATUS_136") (pintype "bidirectional"))
      (node (ref "U6") (pin "19") (pinfunction "ADBUS3_19") (pintype "bidirectional"))
    )
    (net (code "36") (name "FT_D4") (class "Default")
      (node (ref "U18") (pin "135") (pinfunction "GPIOL_72_EXTFB0_CDI14_135") (pintype "bidirectional"))
      (node (ref "U6") (pin "21") (pinfunction "ADBUS4_21") (pintype "bidirectional"))
    )
    (net (code "37") (name "FT_D5") (class "Default")
      (node (ref "U18") (pin "134") (pinfunction "GPIOL_73_EXTFB1_CDI15_134") (pintype "bidirectional"))
      (node (ref "U6") (pin "22") (pinfunction "ADBUS5_22") (pintype "bidirectional"))
    )
    (net (code "38") (name "FT_D6") (class "Default")
      (node (ref "U18") (pin "132") (pinfunction "GPIOL_74_PLLIN0_132") (pintype "bidirectional"))
      (node (ref "U6") (pin "23") (pinfunction "ADBUS6_23") (pintype "bidirectional"))
    )
    (net (code "39") (name "FT_D7") (class "Default")
      (node (ref "U18") (pin "131") (pinfunction "GPIOL_75_PLLIN1_131") (pintype "bidirectional"))
      (node (ref "U6") (pin "24") (pinfunction "ADBUS7_24") (pintype "bidirectional"))
    )
    (net (code "40") (name "FT_NOE") (class "Default")
      (node (ref "U18") (pin "115") (pinfunction "GPIOR_82_115") (pintype "bidirectional"))
      (node (ref "U6") (pin "33") (pinfunction "ACBUS6_33") (pintype "bidirectional"))
    )
    (net (code "41") (name "FT_NPWREN") (class "Default")
      (node (ref "U18") (pin "100") (pinfunction "GPIOR_113_CDI22_100") (pintype "bidirectional"))
      (node (ref "U6") (pin "60") (pinfunction "~{PWREN}_60") (pintype "bidirectional"))
    )
    (net (code "42") (name "FT_NRD") (class "Default")
      (node (ref "U18") (pin "119") (pinfunction "GPIOR_78_EXTFB0_CDI31_119") (pintype "bidirectional"))
      (node (ref "U6") (pin "28") (pinfunction "ACBUS2_28") (pintype "bidirectional"))
    )
    (net (code "43") (name "FT_NRST") (class "Default")
      (node (ref "U18") (pin "124") (pinfunction "GPIOR_76_PLLIN0_124") (pintype "bidirectional"))
      (node (ref "U6") (pin "14") (pinfunction "~{RESET}_14") (pintype "bidirectional"))
    )
    (net (code "44") (name "FT_NRXF") (class "Default")
      (node (ref "U18") (pin "117") (pinfunction "GPIOR_80_117") (pintype "bidirectional"))
      (node (ref "U6") (pin "26") (pinfunction "ACBUS0_26") (pintype "bidirectional"))
    )
    (net (code "45") (name "FT_NSIWU") (class "Default")
      (node (ref "U18") (pin "114") (pinfunction "GPIOR_83_114") (pintype "bidirectional"))
      (node (ref "U6") (pin "30") (pinfunction "ACBUS4_30") (pintype "bidirectional"))
    )
    (net (code "46") (name "FT_NSUSPEND") (class "Default")
      (node (ref "U18") (pin "113") (pinfunction "GPIOR_84_113") (pintype "bidirectional"))
      (node (ref "U6") (pin "36") (pinfunction "~{SUSPEND}_36") (pintype "bidirectional"))
    )
    (net (code "47") (name "FT_NTXE") (class "Default")
      (node (ref "U18") (pin "116") (pinfunction "GPIOR_81_MREFCLK_116") (pintype "bidirectional"))
      (node (ref "U6") (pin "27") (pinfunction "ACBUS1_27") (pintype "bidirectional"))
    )
    (net (code "48") (name "FT_NWR") (class "Default")
      (node (ref "U18") (pin "118") (pinfunction "GPIOR_79_EXTFB1_CDI30_118") (pintype "bidirectional"))
      (node (ref "U6") (pin "29") (pinfunction "ACBUS3_29") (pintype "bidirectional"))
    )
    (net (code "49") (name "GND") (class "Default")
      (node (ref "C10") (pin "1") (pinfunction "1_1") (pintype "bidirectional"))
      (node (ref "C11") (pin "1") (pinfunction "1_1") (pintype "bidirectional"))
      (node (ref "C12") (pin "1") (pinfunction "1_1") (pintype "bidirectional"))
      (node (ref "C13") (pin "1") (pinfunction "1_1") (pintype "bidirectional"))
      (node (ref "C14") (pin "1") (pinfunction "1_1") (pintype "bidirectional"))
      (node (ref "C15") (pin "1") (pinfunction "1_1") (pintype "bidirectional"))
      (node (ref "C16") (pin "1") (pinfunction "1_1") (pintype "bidirectional"))
      (node (ref "C17") (pin "1") (pinfunction "1_1") (pintype "bidirectional"))
      (node (ref "C18") (pin "1") (pinfunction "1_1") (pintype "bidirectional"))
      (node (ref "C19") (pin "1") (pinfunction "1_1") (pintype "bidirectional"))
      (node (ref "C2") (pin "N") (pinfunction "K_N") (pintype "bidirectional"))
      (node (ref "C20") (pin "1") (pinfunction "1_1") (pintype "bidirectional"))
      (node (ref "C21") (pin "1") (pinfunction "1_1") (pintype "bidirectional"))
      (node (ref "C22") (pin "1") (pinfunction "1_1") (pintype "bidirectional"))
      (node (ref "C23") (pin "1") (pinfunction "1_1") (pintype "bidirectional"))
      (node (ref "C24") (pin "1") (pinfunction "1_1") (pintype "bidirectional"))
      (node (ref "C25") (pin "1") (pinfunction "1_1") (pintype "bidirectional"))
      (node (ref "C26") (pin "1") (pinfunction "1_1") (pintype "bidirectional"))
      (node (ref "C27") (pin "1") (pinfunction "1_1") (pintype "bidirectional"))
      (node (ref "C28") (pin "2") (pinfunction "2_2") (pintype "bidirectional"))
      (node (ref "C29") (pin "1") (pinfunction "1_1") (pintype "bidirectional"))
      (node (ref "C30") (pin "1") (pinfunction "1_1") (pintype "bidirectional"))
      (node (ref "C31") (pin "1") (pinfunction "1_1") (pintype "bidirectional"))
      (node (ref "C32") (pin "1") (pinfunction "1_1") (pintype "bidirectional"))
      (node (ref "C33") (pin "1") (pinfunction "1_1") (pintype "bidirectional"))
      (node (ref "C34") (pin "1") (pinfunction "1_1") (pintype "bidirectional"))
      (node (ref "C35") (pin "1") (pinfunction "1_1") (pintype "bidirectional"))
      (node (ref "C36") (pin "1") (pinfunction "1_1") (pintype "bidirectional"))
      (node (ref "C37") (pin "1") (pinfunction "1_1") (pintype "bidirectional"))
      (node (ref "C38") (pin "1") (pinfunction "1_1") (pintype "bidirectional"))
      (node (ref "C4") (pin "1") (pinfunction "1_1") (pintype "bidirectional"))
      (node (ref "C40") (pin "1") (pinfunction "1_1") (pintype "bidirectional"))
      (node (ref "C41") (pin "1") (pinfunction "1_1") (pintype "bidirectional"))
      (node (ref "C42") (pin "1") (pinfunction "1_1") (pintype "bidirectional"))
      (node (ref "C44") (pin "1") (pinfunction "1_1") (pintype "bidirectional"))
      (node (ref "C45") (pin "1") (pinfunction "1_1") (pintype "bidirectional"))
      (node (ref "C46") (pin "1") (pinfunction "1_1") (pintype "bidirectional"))
      (node (ref "C47") (pin "1") (pinfunction "1_1") (pintype "bidirectional"))
      (node (ref "C5") (pin "1") (pinfunction "1_1") (pintype "bidirectional"))
      (node (ref "C52") (pin "1") (pinfunction "1_1") (pintype "bidirectional"))
      (node (ref "C53") (pin "1") (pinfunction "1_1") (pintype "bidirectional"))
      (node (ref "C54") (pin "1") (pinfunction "1_1") (pintype "bidirectional"))
      (node (ref "C55") (pin "1") (pinfunction "1_1") (pintype "bidirectional"))
      (node (ref "C56") (pin "1") (pinfunction "1_1") (pintype "bidirectional"))
      (node (ref "C57") (pin "1") (pinfunction "1_1") (pintype "bidirectional"))
      (node (ref "C58") (pin "1") (pinfunction "1_1") (pintype "bidirectional"))
      (node (ref "C59") (pin "1") (pinfunction "1_1") (pintype "bidirectional"))
      (node (ref "C6") (pin "N") (pinfunction "K_N") (pintype "bidirectional"))
      (node (ref "C64") (pin "1") (pinfunction "1_1") (pintype "bidirectional"))
      (node (ref "C65") (pin "1") (pinfunction "1_1") (pintype "bidirectional"))
      (node (ref "C66") (pin "1") (pinfunction "1_1") (pintype "bidirectional"))
      (node (ref "C67") (pin "2") (pinfunction "K_2") (pintype "bidirectional"))
      (node (ref "C68") (pin "1") (pinfunction "1_1") (pintype "bidirectional"))
      (node (ref "C8") (pin "1") (pinfunction "1_1") (pintype "bidirectional"))
      (node (ref "C9") (pin "1") (pinfunction "1_1") (pintype "bidirectional"))
      (node (ref "CN1") (pin "A12B1") (pinfunction "GND_A12B1") (pintype "bidirectional"))
      (node (ref "CN1") (pin "B12A1") (pinfunction "GND_B12A1") (pintype "bidirectional"))
      (node (ref "CN1") (pin "P$1") (pinfunction "GND_P$1") (pintype "bidirectional"))
      (node (ref "CN1") (pin "P$10") (pinfunction "GND_P$10") (pintype "bidirectional"))
      (node (ref "CN1") (pin "P$11") (pinfunction "GND_P$11") (pintype "bidirectional"))
      (node (ref "CN1") (pin "P$12") (pinfunction "GND_P$12") (pintype "bidirectional"))
      (node (ref "CN1") (pin "P$13") (pinfunction "GND_P$13") (pintype "bidirectional"))
      (node (ref "CN1") (pin "P$14") (pinfunction "GND_P$14") (pintype "bidirectional"))
      (node (ref "CN1") (pin "P$15") (pinfunction "GND_P$15") (pintype "bidirectional"))
      (node (ref "CN1") (pin "P$16") (pinfunction "GND_P$16") (pintype "bidirectional"))
      (node (ref "CN1") (pin "P$17") (pinfunction "GND_P$17") (pintype "bidirectional"))
      (node (ref "CN1") (pin "P$18") (pinfunction "GND_P$18") (pintype "bidirectional"))
      (node (ref "CN1") (pin "P$19") (pinfunction "GND_P$19") (pintype "bidirectional"))
      (node (ref "CN1") (pin "P$2") (pinfunction "GND_P$2") (pintype "bidirectional"))
      (node (ref "CN1") (pin "P$20") (pinfunction "GND_P$20") (pintype "bidirectional"))
      (node (ref "CN1") (pin "P$21") (pinfunction "GND_P$21") (pintype "bidirectional"))
      (node (ref "CN1") (pin "P$22") (pinfunction "GND_P$22") (pintype "bidirectional"))
      (node (ref "CN1") (pin "P$23") (pinfunction "GND_P$23") (pintype "bidirectional"))
      (node (ref "CN1") (pin "P$24") (pinfunction "GND_P$24") (pintype "bidirectional"))
      (node (ref "CN1") (pin "P$3") (pinfunction "GND_P$3") (pintype "bidirectional"))
      (node (ref "CN1") (pin "P$4") (pinfunction "GND_P$4") (pintype "bidirectional"))
      (node (ref "CN1") (pin "P$5") (pinfunction "GND_P$5") (pintype "bidirectional"))
      (node (ref "CN1") (pin "P$6") (pinfunction "GND_P$6") (pintype "bidirectional"))
      (node (ref "CN1") (pin "P$7") (pinfunction "GND_P$7") (pintype "bidirectional"))
      (node (ref "CN1") (pin "P$8") (pinfunction "GND_P$8") (pintype "bidirectional"))
      (node (ref "CN1") (pin "P$9") (pinfunction "GND_P$9") (pintype "bidirectional"))
      (node (ref "CN2") (pin "4") (pinfunction "4_4") (pintype "bidirectional"))
      (node (ref "CN2") (pin "5") (pinfunction "5_5") (pintype "bidirectional"))
      (node (ref "CN2") (pin "6") (pinfunction "6_6") (pintype "bidirectional"))
      (node (ref "CN2") (pin "7") (pinfunction "7_7") (pintype "bidirectional"))
      (node (ref "CN4") (pin "8") (pinfunction "8_8") (pintype "bidirectional"))
      (node (ref "CN5") (pin "3") (pinfunction "GND_3") (pintype "bidirectional"))
      (node (ref "CN7") (pin "8") (pinfunction "8_8") (pintype "bidirectional"))
      (node (ref "D2") (pin "A") (pinfunction "A_A") (pintype "bidirectional"))
      (node (ref "D3") (pin "A") (pinfunction "A_A") (pintype "bidirectional"))
      (node (ref "OSC1") (pin "2") (pinfunction "GND_2") (pintype "bidirectional"))
      (node (ref "R126") (pin "1") (pinfunction "1_1") (pintype "bidirectional"))
      (node (ref "R149") (pin "1") (pinfunction "1_1") (pintype "bidirectional"))
      (node (ref "R15") (pin "1") (pinfunction "1_1") (pintype "bidirectional"))
      (node (ref "R16") (pin "2") (pinfunction "2_2") (pintype "bidirectional"))
      (node (ref "R17") (pin "2") (pinfunction "2_2") (pintype "bidirectional"))
      (node (ref "R19") (pin "1") (pinfunction "1_1") (pintype "bidirectional"))
      (node (ref "R6") (pin "1") (pinfunction "1_1") (pintype "bidirectional"))
      (node (ref "SW1") (pin "2") (pinfunction "1_2") (pintype "bidirectional"))
      (node (ref "U1") (pin "1") (pinfunction "GND_1") (pintype "bidirectional"))
      (node (ref "U18") (pin "1") (pinfunction "GND_1") (pintype "bidirectional"))
      (node (ref "U18") (pin "104") (pinfunction "GND_104") (pintype "bidirectional"))
      (node (ref "U18") (pin "108") (pinfunction "GND_108") (pintype "bidirectional"))
      (node (ref "U18") (pin "120") (pinfunction "GND_120") (pintype "bidirectional"))
      (node (ref "U18") (pin "121") (pinfunction "GND_121") (pintype "bidirectional"))
      (node (ref "U18") (pin "126") (pinfunction "GND_126") (pintype "bidirectional"))
      (node (ref "U18") (pin "127") (pinfunction "GND_127") (pintype "bidirectional"))
      (node (ref "U18") (pin "129") (pinfunction "GND_129") (pintype "bidirectional"))
      (node (ref "U18") (pin "133") (pinfunction "GND_133") (pintype "bidirectional"))
      (node (ref "U18") (pin "37") (pinfunction "GND_37") (pintype "bidirectional"))
      (node (ref "U18") (pin "44") (pinfunction "GND_44") (pintype "bidirectional"))
      (node (ref "U18") (pin "5") (pinfunction "GND_5") (pintype "bidirectional"))
      (node (ref "U18") (pin "50") (pinfunction "GND_50") (pintype "bidirectional"))
      (node (ref "U18") (pin "64") (pinfunction "GND_64") (pintype "bidirectional"))
      (node (ref "U18") (pin "9") (pinfunction "GND_9") (pintype "bidirectional"))
      (node (ref "U18") (pin "94") (pinfunction "GND_94") (pintype "bidirectional"))
      (node (ref "U2") (pin "2") (pinfunction "GND_2") (pintype "bidirectional"))
      (node (ref "U23") (pin "18") (pinfunction "GND_18") (pintype "bidirectional"))
      (node (ref "U23") (pin "29") (pinfunction "GND_29") (pintype "bidirectional"))
      (node (ref "U23") (pin "3") (pinfunction "GND_3") (pintype "bidirectional"))
      (node (ref "U3") (pin "5") (pinfunction "GND_5") (pintype "bidirectional"))
      (node (ref "U4") (pin "4") (pinfunction "GND_4") (pintype "bidirectional"))
      (node (ref "U5") (pin "1") (pinfunction "GND_1") (pintype "bidirectional"))
      (node (ref "U5") (pin "3") (pinfunction "GND_3") (pintype "bidirectional"))
      (node (ref "U5") (pin "6") (pinfunction "MODE_6") (pintype "bidirectional"))
      (node (ref "U5") (pin "PAD") (pinfunction "GND_PAD") (pintype "bidirectional"))
      (node (ref "U6") (pin "1") (pinfunction "GND_1") (pintype "bidirectional"))
      (node (ref "U6") (pin "10") (pinfunction "GND_10") (pintype "bidirectional"))
      (node (ref "U6") (pin "11") (pinfunction "GND_11") (pintype "bidirectional"))
      (node (ref "U6") (pin "13") (pinfunction "TEST_13") (pintype "bidirectional"))
      (node (ref "U6") (pin "15") (pinfunction "GND_15") (pintype "bidirectional"))
      (node (ref "U6") (pin "25") (pinfunction "GND_25") (pintype "bidirectional"))
      (node (ref "U6") (pin "35") (pinfunction "GND_35") (pintype "bidirectional"))
      (node (ref "U6") (pin "47") (pinfunction "GND_47") (pintype "bidirectional"))
      (node (ref "U6") (pin "5") (pinfunction "GND_5") (pintype "bidirectional"))
      (node (ref "U6") (pin "51") (pinfunction "GND_51") (pintype "bidirectional"))
      (node (ref "U6") (pin "PAD") (pinfunction "GND_PAD") (pintype "bidirectional"))
      (node (ref "U7") (pin "1") (pinfunction "GND_1") (pintype "bidirectional"))
      (node (ref "XTAL2") (pin "2") (pinfunction "GND_2") (pintype "bidirectional"))
      (node (ref "XTAL2") (pin "4") (pinfunction "GND_4") (pintype "bidirectional"))
    )
    (net (code "50") (name "GPIOB_N0") (class "Default")
      (node (ref "U18") (pin "56") (pinfunction "GPIOB_RXN00_56") (pintype "bidirectional"))
    )
    (net (code "51") (name "GPIOB_N2") (class "Default")
      (node (ref "U18") (pin "59") (pinfunction "GPIOB_RXN02_59") (pintype "bidirectional"))
    )
    (net (code "52") (name "GPIOB_N3") (class "Default")
      (node (ref "U18") (pin "60") (pinfunction "GPIOB_RXN03_60") (pintype "bidirectional"))
    )
    (net (code "53") (name "GPIOB_N7") (class "Default")
      (node (ref "U18") (pin "65") (pinfunction "GPIOB_RXN07_65") (pintype "bidirectional"))
    )
    (net (code "54") (name "GPIOB_P0") (class "Default")
      (node (ref "U18") (pin "55") (pinfunction "GPIOB_RXP00_55") (pintype "bidirectional"))
    )
    (net (code "55") (name "GPIOB_P2") (class "Default")
      (node (ref "U18") (pin "58") (pinfunction "GPIOB_RXP02_58") (pintype "bidirectional"))
    )
    (net (code "56") (name "GPIOB_P3") (class "Default")
      (node (ref "U18") (pin "61") (pinfunction "GPIOB_RXP03_61") (pintype "bidirectional"))
    )
    (net (code "57") (name "GPIOB_P7") (class "Default")
      (node (ref "U18") (pin "66") (pinfunction "GPIOB_RXP07_66") (pintype "bidirectional"))
    )
    (net (code "58") (name "GPIOB_TN0") (class "Default")
      (node (ref "U18") (pin "39") (pinfunction "GPIOB_TXN00_39") (pintype "bidirectional"))
    )
    (net (code "59") (name "GPIOB_TN2") (class "Default")
      (node (ref "U18") (pin "41") (pinfunction "GPIOB_TXN02_41") (pintype "bidirectional"))
    )
    (net (code "60") (name "GPIOB_TN4") (class "Default")
      (node (ref "U18") (pin "43") (pinfunction "GPIOB_TXN04_43") (pintype "bidirectional"))
    )
    (net (code "61") (name "GPIOB_TN6") (class "Default")
      (node (ref "U18") (pin "46") (pinfunction "GPIOB_TXN06_46") (pintype "bidirectional"))
    )
    (net (code "62") (name "GPIOB_TN9") (class "Default")
      (node (ref "U18") (pin "48") (pinfunction "GPIOB_TXN09_48") (pintype "bidirectional"))
    )
    (net (code "63") (name "GPIOB_TN11") (class "Default")
      (node (ref "U18") (pin "54") (pinfunction "GPIOB_TXN11_54") (pintype "bidirectional"))
    )
    (net (code "64") (name "GPIOB_TP0") (class "Default")
      (node (ref "U18") (pin "38") (pinfunction "GPIOB_TXP00_38") (pintype "bidirectional"))
    )
    (net (code "65") (name "GPIOB_TP2") (class "Default")
      (node (ref "U18") (pin "40") (pinfunction "GPIOB_TXP02_40") (pintype "bidirectional"))
    )
    (net (code "66") (name "GPIOB_TP4") (class "Default")
      (node (ref "U18") (pin "42") (pinfunction "GPIOB_TXP04_42") (pintype "bidirectional"))
    )
    (net (code "67") (name "GPIOB_TP6") (class "Default")
      (node (ref "U18") (pin "45") (pinfunction "GPIOB_TXP06_45") (pintype "bidirectional"))
    )
    (net (code "68") (name "GPIOB_TP9") (class "Default")
      (node (ref "U18") (pin "47") (pinfunction "GPIOB_TXP09_47") (pintype "bidirectional"))
    )
    (net (code "69") (name "GPIOB_TP11") (class "Default")
      (node (ref "U18") (pin "53") (pinfunction "GPIOB_TXP11_53") (pintype "bidirectional"))
    )
    (net (code "70") (name "GPIOL_12") (class "Default")
      (node (ref "U18") (pin "20") (pinfunction "GPIOL_12_CDI2_20") (pintype "bidirectional"))
    )
    (net (code "71") (name "GPIOL_13") (class "Default")
      (node (ref "U18") (pin "19") (pinfunction "GPIOL_13_CDI3_19") (pintype "bidirectional"))
    )
    (net (code "72") (name "GPIOL_20") (class "Default")
      (node (ref "U18") (pin "18") (pinfunction "GPIOL_20_CTRL0_CDI4_18") (pintype "bidirectional"))
    )
    (net (code "73") (name "GPIOL_21") (class "Default")
      (node (ref "U18") (pin "17") (pinfunction "GPIOL_21_CTRL1_CDI5_17") (pintype "bidirectional"))
    )
    (net (code "74") (name "GPIOL_22") (class "Default")
      (node (ref "U18") (pin "16") (pinfunction "GPIOL_22_CTRL2_16") (pintype "bidirectional"))
    )
    (net (code "75") (name "GPIOL_24") (class "Default")
      (node (ref "U18") (pin "15") (pinfunction "GPIOL_24_CLK0_15") (pintype "bidirectional"))
    )
    (net (code "76") (name "GPIOL_25") (class "Default")
      (node (ref "U18") (pin "14") (pinfunction "GPIOL_25_CLK1_14") (pintype "bidirectional"))
    )
    (net (code "77") (name "GPIOL_31") (class "Default")
      (node (ref "U18") (pin "11") (pinfunction "GPIOL_31_CLK7_CDI6_11") (pintype "bidirectional"))
    )
    (net (code "78") (name "GPIOL_32") (class "Default")
      (node (ref "U18") (pin "10") (pinfunction "GPIOL_32_CTRL4_CDI7_10") (pintype "bidirectional"))
    )
    (net (code "79") (name "GPIOL_40") (class "Default")
      (node (ref "U18") (pin "8") (pinfunction "GPIOL_40_CDI8_8") (pintype "bidirectional"))
    )
    (net (code "80") (name "GPIOL_41") (class "Default")
      (node (ref "U18") (pin "7") (pinfunction "GPIOL_41_CDI9_7") (pintype "bidirectional"))
    )
    (net (code "81") (name "GPIOL_46") (class "Default")
      (node (ref "U18") (pin "6") (pinfunction "GPIOL_46_6") (pintype "bidirectional"))
    )
    (net (code "82") (name "GPIOL_53") (class "Default")
      (node (ref "U18") (pin "3") (pinfunction "GPIOL_53_CDI10_3") (pintype "bidirectional"))
    )
    (net (code "83") (name "GPIOL_54") (class "Default")
      (node (ref "U18") (pin "4") (pinfunction "GPIOL_54_CDI11_4") (pintype "bidirectional"))
    )
    (net (code "84") (name "GPIOL_64") (class "Default")
      (node (ref "U18") (pin "144") (pinfunction "GPIOL_64_144") (pintype "bidirectional"))
    )
    (net (code "85") (name "GPIOL_65") (class "Default")
      (node (ref "U18") (pin "141") (pinfunction "GPIOL_65_141") (pintype "bidirectional"))
    )
    (net (code "86") (name "GPIOL_66") (class "Default")
      (node (ref "U18") (pin "142") (pinfunction "GPIOL_66_CDI12_142") (pintype "bidirectional"))
    )
    (net (code "87") (name "GPIOL_67") (class "Default")
      (node (ref "U18") (pin "140") (pinfunction "GPIOL_67_CDI13_140") (pintype "bidirectional"))
    )
    (net (code "88") (name "GPIOR_128") (class "Default")
      (node (ref "U18") (pin "90") (pinfunction "GPIOR_128_CTRL11_90") (pintype "bidirectional"))
    )
    (net (code "89") (name "GPIOR_129") (class "Default")
      (node (ref "U18") (pin "89") (pinfunction "GPIOR_129_CTRL10_89") (pintype "bidirectional"))
    )
    (net (code "90") (name "GPIOR_132") (class "Default")
      (node (ref "U18") (pin "87") (pinfunction "GPIOR_132_CDI19_87") (pintype "bidirectional"))
    )
    (net (code "91") (name "GPIOR_133") (class "Default")
      (node (ref "U18") (pin "86") (pinfunction "GPIOR_133_CDI18_86") (pintype "bidirectional"))
    )
    (net (code "92") (name "LED_PWM_CONT") (class "Default")
      (node (ref "CN2") (pin "3") (pinfunction "3_3") (pintype "bidirectional"))
    )
    (net (code "93") (name "Net-(C2-A)") (class "Default")
      (node (ref "C2") (pin "P") (pinfunction "A_P") (pintype "bidirectional"))
      (node (ref "C7") (pin "1") (pinfunction "1_1") (pintype "bidirectional"))
      (node (ref "D1") (pin "K") (pinfunction "K_K") (pintype "bidirectional"))
      (node (ref "D2") (pin "K") (pinfunction "K_K") (pintype "bidirectional"))
      (node (ref "D4") (pin "K") (pinfunction "K_K") (pintype "bidirectional"))
      (node (ref "Q1") (pin "1") (pinfunction "S_1") (pintype "bidirectional"))
      (node (ref "Q1") (pin "2") (pinfunction "S_2") (pintype "bidirectional"))
      (node (ref "Q1") (pin "3") (pinfunction "S_3") (pintype "bidirectional"))
      (node (ref "R1") (pin "1") (pinfunction "1_1") (pintype "bidirectional"))
    )
    (net (code "94") (name "Net-(C3-Pad2)") (class "Default")
      (node (ref "C3") (pin "2") (pinfunction "2_2") (pintype "bidirectional"))
      (node (ref "R2") (pin "1") (pinfunction "1_1") (pintype "bidirectional"))
      (node (ref "R4") (pin "2") (pinfunction "2_2") (pintype "bidirectional"))
    )
    (net (code "95") (name "Net-(CN1-VBUS-PadA9B4)") (class "Default")
      (node (ref "CN1") (pin "A9B4") (pinfunction "VBUS_A9B4") (pintype "bidirectional"))
      (node (ref "CN1") (pin "B9A4") (pinfunction "VBUS_B9A4") (pintype "bidirectional"))
      (node (ref "FB3") (pin "1") (pinfunction "1_1") (pintype "bidirectional"))
    )
    (net (code "96") (name "Net-(CN5-V+)") (class "Default")
      (node (ref "CN5") (pin "1") (pinfunction "V+_1") (pintype "bidirectional"))
      (node (ref "D1") (pin "A") (pinfunction "A_A") (pintype "bidirectional"))
      (node (ref "D3") (pin "K") (pinfunction "K_K") (pintype "bidirectional"))
    )
    (net (code "97") (name "Net-(D5-PadA)") (class "Default")
      (node (ref "D5") (pin "A") (pinfunction "A_A") (pintype "bidirectional"))
      (node (ref "R11") (pin "1") (pinfunction "1_1") (pintype "bidirectional"))
    )
    (net (code "98") (name "Net-(D6-PadA)") (class "Default")
      (node (ref "D6") (pin "A") (pinfunction "A_A") (pintype "bidirectional"))
      (node (ref "R12") (pin "1") (pinfunction "1_1") (pintype "bidirectional"))
    )
    (net (code "99") (name "Net-(D7-PadA)") (class "Default")
      (node (ref "D7") (pin "A") (pinfunction "A_A") (pintype "bidirectional"))
      (node (ref "R13") (pin "1") (pinfunction "1_1") (pintype "bidirectional"))
    )
    (net (code "100") (name "Net-(D8-PadA)") (class "Default")
      (node (ref "D8") (pin "A") (pinfunction "A_A") (pintype "bidirectional"))
      (node (ref "R14") (pin "1") (pinfunction "1_1") (pintype "bidirectional"))
    )
    (net (code "101") (name "Net-(D10-PadA)") (class "Default")
      (node (ref "D10") (pin "A") (pinfunction "A_A") (pintype "bidirectional"))
      (node (ref "R59") (pin "1") (pinfunction "1_1") (pintype "bidirectional"))
    )
    (net (code "102") (name "Net-(Q1-G)") (class "Default")
      (node (ref "C7") (pin "2") (pinfunction "2_2") (pintype "bidirectional"))
      (node (ref "D4") (pin "A") (pinfunction "A_A") (pintype "bidirectional"))
      (node (ref "Q1") (pin "4") (pinfunction "G_4") (pintype "bidirectional"))
      (node (ref "R1") (pin "2") (pinfunction "2_2") (pintype "bidirectional"))
      (node (ref "R5") (pin "2") (pinfunction "2_2") (pintype "bidirectional"))
    )
    (net (code "103") (name "Net-(R5-Pad1)") (class "Default")
      (node (ref "R5") (pin "1") (pinfunction "1_1") (pintype "bidirectional"))
      (node (ref "SW1") (pin "3") (pinfunction "3_3") (pintype "bidirectional"))
    )
    (net (code "104") (name "Net-(U1-BOOT)") (class "Default")
      (node (ref "C1") (pin "1") (pinfunction "1_1") (pintype "bidirectional"))
      (node (ref "U1") (pin "6") (pinfunction "BOOT_6") (pintype "bidirectional"))
    )
    (net (code "105") (name "Net-(U1-FB)") (class "Default")
      (node (ref "C3") (pin "1") (pinfunction "1_1") (pintype "bidirectional"))
      (node (ref "R15") (pin "2") (pinfunction "2_2") (pintype "bidirectional"))
      (node (ref "R4") (pin "1") (pinfunction "1_1") (pintype "bidirectional"))
      (node (ref "U1") (pin "4") (pinfunction "FB_4") (pintype "bidirectional"))
    )
    (net (code "106") (name "Net-(U1-SW)") (class "Default")
      (node (ref "C1") (pin "2") (pinfunction "2_2") (pintype "bidirectional"))
      (node (ref "L1") (pin "1") (pinfunction "1_1") (pintype "bidirectional"))
      (node (ref "U1") (pin "2") (pinfunction "SW_2") (pintype "bidirectional"))
    )
    (net (code "107") (name "Net-(U2-D+_IN)") (class "Default")
      (node (ref "CN1") (pin "A7") (pinfunction "D-_A7") (pintype "bidirectional"))
      (node (ref "CN1") (pin "B7") (pinfunction "D-_B7") (pintype "bidirectional"))
      (node (ref "U2") (pin "1") (pinfunction "D+_IN_1") (pintype "bidirectional"))
    )
    (net (code "108") (name "Net-(U2-D-_IN)") (class "Default")
      (node (ref "CN1") (pin "A6") (pinfunction "D+_A6") (pintype "bidirectional"))
      (node (ref "CN1") (pin "B6") (pinfunction "D+_B6") (pintype "bidirectional"))
      (node (ref "U2") (pin "3") (pinfunction "D-_IN_3") (pintype "bidirectional"))
    )
    (net (code "109") (name "Net-(U3-CLK)") (class "Default")
      (node (ref "R8") (pin "1") (pinfunction "1_1") (pintype "bidirectional"))
      (node (ref "U3") (pin "2") (pinfunction "CLK_2") (pintype "bidirectional"))
      (node (ref "U6") (pin "62") (pinfunction "EECLK_62") (pintype "bidirectional"))
    )
    (net (code "110") (name "Net-(U3-CS)") (class "Default")
      (node (ref "R7") (pin "1") (pinfunction "1_1") (pintype "bidirectional"))
      (node (ref "U3") (pin "1") (pinfunction "CS_1") (pintype "bidirectional"))
      (node (ref "U6") (pin "63") (pinfunction "EECS_63") (pintype "bidirectional"))
    )
    (net (code "111") (name "Net-(U3-DI)") (class "Default")
      (node (ref "R10") (pin "2") (pinfunction "2_2") (pintype "bidirectional"))
      (node (ref "U3") (pin "3") (pinfunction "DI_3") (pintype "bidirectional"))
      (node (ref "U6") (pin "61") (pinfunction "EEDATA_61") (pintype "bidirectional"))
    )
    (net (code "112") (name "Net-(U3-DO)") (class "Default")
      (node (ref "R10") (pin "1") (pinfunction "1_1") (pintype "bidirectional"))
      (node (ref "R9") (pin "1") (pinfunction "1_1") (pintype "bidirectional"))
      (node (ref "U3") (pin "4") (pinfunction "DO_4") (pintype "bidirectional"))
    )
    (net (code "113") (name "Net-(U4-~{WP}{slash}IO2)") (class "Default")
      (node (ref "R137") (pin "1") (pinfunction "1_1") (pintype "bidirectional"))
      (node (ref "U4") (pin "3") (pinfunction "~{WP}/IO2_3") (pintype "bidirectional"))
    )
    (net (code "114") (name "Net-(U5-FB)") (class "Default")
      (node (ref "C39") (pin "1") (pinfunction "1_1") (pintype "bidirectional"))
      (node (ref "R148") (pin "1") (pinfunction "1_1") (pintype "bidirectional"))
      (node (ref "R149") (pin "2") (pinfunction "2_2") (pintype "bidirectional"))
      (node (ref "U5") (pin "4") (pinfunction "FB_4") (pintype "bidirectional"))
    )
    (net (code "115") (name "Net-(U5-SW)") (class "Default")
      (node (ref "L3") (pin "1") (pinfunction "1_1") (pintype "bidirectional"))
      (node (ref "U5") (pin "2") (pinfunction "SW_2") (pintype "bidirectional"))
    )
    (net (code "116") (name "Net-(U6-REF)") (class "Default")
      (node (ref "R6") (pin "2") (pinfunction "2_2") (pintype "bidirectional"))
      (node (ref "U6") (pin "6") (pinfunction "REF_6") (pintype "bidirectional"))
    )
    (net (code "117") (name "Net-(U6-VREGOUT)") (class "Default")
      (node (ref "C55") (pin "2") (pinfunction "2_2") (pintype "bidirectional"))
      (node (ref "C56") (pin "2") (pinfunction "2_2") (pintype "bidirectional"))
      (node (ref "C57") (pin "2") (pinfunction "2_2") (pintype "bidirectional"))
      (node (ref "C58") (pin "2") (pinfunction "2_2") (pintype "bidirectional"))
      (node (ref "U6") (pin "12") (pinfunction "VCORE_12") (pintype "bidirectional"))
      (node (ref "U6") (pin "37") (pinfunction "VCORE_37") (pintype "bidirectional"))
      (node (ref "U6") (pin "49") (pinfunction "VREGOUT_49") (pintype "bidirectional"))
      (node (ref "U6") (pin "64") (pinfunction "VCORE_64") (pintype "bidirectional"))
    )
    (net (code "118") (name "Net-(U6-XCSI)") (class "Default")
      (node (ref "C24") (pin "2") (pinfunction "2_2") (pintype "bidirectional"))
      (node (ref "U6") (pin "2") (pinfunction "XCSI_2") (pintype "bidirectional"))
      (node (ref "XTAL2") (pin "1") (pinfunction "P$1_1") (pintype "bidirectional"))
    )
    (net (code "119") (name "Net-(U6-XCSO)") (class "Default")
      (node (ref "C23") (pin "2") (pinfunction "2_2") (pintype "bidirectional"))
      (node (ref "U6") (pin "3") (pinfunction "XCSO_3") (pintype "bidirectional"))
      (node (ref "XTAL2") (pin "3") (pinfunction "P$2_3") (pintype "bidirectional"))
    )
    (net (code "120") (name "Net-(U7-BOOT)") (class "Default")
      (node (ref "C43") (pin "1") (pinfunction "1_1") (pintype "bidirectional"))
      (node (ref "U7") (pin "6") (pinfunction "BOOT_6") (pintype "bidirectional"))
    )
    (net (code "121") (name "Net-(U7-FB)") (class "Default")
      (node (ref "C48") (pin "1") (pinfunction "1_1") (pintype "bidirectional"))
      (node (ref "R18") (pin "1") (pinfunction "1_1") (pintype "bidirectional"))
      (node (ref "R19") (pin "2") (pinfunction "2_2") (pintype "bidirectional"))
      (node (ref "U7") (pin "4") (pinfunction "FB_4") (pintype "bidirectional"))
    )
    (net (code "122") (name "Net-(U7-SW)") (class "Default")
      (node (ref "C43") (pin "2") (pinfunction "2_2") (pintype "bidirectional"))
      (node (ref "L2") (pin "1") (pinfunction "1_1") (pintype "bidirectional"))
      (node (ref "U7") (pin "2") (pinfunction "SW_2") (pintype "bidirectional"))
    )
    (net (code "123") (name "Net-(U18-REF_RES)") (class "Default")
      (node (ref "R126") (pin "2") (pinfunction "2_2") (pintype "bidirectional"))
      (node (ref "U18") (pin "36") (pinfunction "REF_RES_36") (pintype "bidirectional"))
    )
    (net (code "124") (name "Net-(U23-5VOUT)") (class "Default")
      (node (ref "C68") (pin "2") (pinfunction "2_2") (pintype "bidirectional"))
      (node (ref "U23") (pin "8") (pinfunction "5VOUT_8") (pintype "bidirectional"))
    )
    (net (code "125") (name "Net-(U23-BRA)") (class "Default")
      (node (ref "R16") (pin "1") (pinfunction "1_1") (pintype "bidirectional"))
      (node (ref "U23") (pin "23") (pinfunction "BRA_23") (pintype "bidirectional"))
    )
    (net (code "126") (name "Net-(U23-BRB)") (class "Default")
      (node (ref "R17") (pin "1") (pinfunction "1_1") (pintype "bidirectional"))
      (node (ref "U23") (pin "27") (pinfunction "BRB_27") (pintype "bidirectional"))
    )
    (net (code "127") (name "Net-(U23-CPI)") (class "Default")
      (node (ref "C70") (pin "2") (pinfunction "2_2") (pintype "bidirectional"))
      (node (ref "U23") (pin "5") (pinfunction "CPI_5") (pintype "bidirectional"))
    )
    (net (code "128") (name "Net-(U23-CPO)") (class "Default")
      (node (ref "C70") (pin "1") (pinfunction "1_1") (pintype "bidirectional"))
      (node (ref "U23") (pin "4") (pinfunction "CPO_4") (pintype "bidirectional"))
    )
    (net (code "129") (name "Net-(U23-VCP)") (class "Default")
      (node (ref "C69") (pin "1") (pinfunction "1_1") (pintype "bidirectional"))
      (node (ref "U23") (pin "6") (pinfunction "VCP_6") (pintype "bidirectional"))
    )
    (net (code "130") (name "PROC_JTAG_TCK") (class "Default")
      (node (ref "CN7") (pin "3") (pinfunction "3_3") (pintype "bidirectional"))
      (node (ref "R20") (pin "1") (pinfunction "1_1") (pintype "bidirectional"))
      (node (ref "U18") (pin "97") (pinfunction "GPIOR_122_CLK13_CDI21_97") (pintype "bidirectional"))
    )
    (net (code "131") (name "PROC_JTAG_TDI") (class "Default")
      (node (ref "CN7") (pin "2") (pinfunction "2_2") (pintype "bidirectional"))
      (node (ref "U18") (pin "98") (pinfunction "GPIOR_117_CTRL14_98") (pintype "bidirectional"))
    )
    (net (code "132") (name "PROC_JTAG_TDO") (class "Default")
      (node (ref "CN7") (pin "5") (pinfunction "5_5") (pintype "bidirectional"))
      (node (ref "R21") (pin "1") (pinfunction "1_1") (pintype "bidirectional"))
      (node (ref "U18") (pin "92") (pinfunction "GPIOR_125_CLK10_92") (pintype "bidirectional"))
    )
    (net (code "133") (name "PROC_JTAG_TMS") (class "Default")
      (node (ref "CN7") (pin "4") (pinfunction "4_4") (pintype "bidirectional"))
      (node (ref "U18") (pin "93") (pinfunction "GPIOR_123_CLK12_CDI20_93") (pintype "bidirectional"))
    )
    (net (code "134") (name "PROC_SCANNING") (class "Default")
      (node (ref "D10") (pin "K") (pinfunction "K_K") (pintype "bidirectional"))
      (node (ref "U18") (pin "81") (pinfunction "GPIOR_139_81") (pintype "bidirectional"))
    )
    (net (code "135") (name "PROC_STATUS") (class "Default")
      (node (ref "D5") (pin "K") (pinfunction "K_K") (pintype "bidirectional"))
      (node (ref "U18") (pin "82") (pinfunction "GPIOR_138_82") (pintype "bidirectional"))
    )
    (net (code "136") (name "PWR_FPGA_1V2") (class "Default")
      (node (ref "C10") (pin "2") (pinfunction "2_2") (pintype "bidirectional"))
      (node (ref "C11") (pin "2") (pinfunction "2_2") (pintype "bidirectional"))
      (node (ref "C12") (pin "2") (pinfunction "2_2") (pintype "bidirectional"))
      (node (ref "C13") (pin "2") (pinfunction "2_2") (pintype "bidirectional"))
      (node (ref "C14") (pin "2") (pinfunction "2_2") (pintype "bidirectional"))
      (node (ref "C15") (pin "2") (pinfunction "2_2") (pintype "bidirectional"))
      (node (ref "C16") (pin "2") (pinfunction "2_2") (pintype "bidirectional"))
      (node (ref "C17") (pin "2") (pinfunction "2_2") (pintype "bidirectional"))
      (node (ref "C26") (pin "2") (pinfunction "2_2") (pintype "bidirectional"))
      (node (ref "C37") (pin "2") (pinfunction "2_2") (pintype "bidirectional"))
      (node (ref "C39") (pin "2") (pinfunction "2_2") (pintype "bidirectional"))
      (node (ref "C8") (pin "2") (pinfunction "2_2") (pintype "bidirectional"))
      (node (ref "C9") (pin "2") (pinfunction "2_2") (pintype "bidirectional"))
      (node (ref "L3") (pin "2") (pinfunction "2_2") (pintype "bidirectional"))
      (node (ref "R148") (pin "2") (pinfunction "2_2") (pintype "bidirectional"))
      (node (ref "U18") (pin "107") (pinfunction "VCCA_TR_107") (pintype "bidirectional"))
      (node (ref "U18") (pin "125") (pinfunction "VCC_125") (pintype "bidirectional"))
      (node (ref "U18") (pin "128") (pinfunction "VCC_128") (pintype "bidirectional"))
      (node (ref "U18") (pin "13") (pinfunction "VCC_13") (pintype "bidirectional"))
      (node (ref "U18") (pin "130") (pinfunction "VCC_130") (pintype "bidirectional"))
      (node (ref "U18") (pin "2") (pinfunction "VCCA_TL_2") (pintype "bidirectional"))
      (node (ref "U18") (pin "22") (pinfunction "VCC_22") (pintype "bidirectional"))
      (node (ref "U18") (pin "49") (pinfunction "VCC_49") (pintype "bidirectional"))
      (node (ref "U18") (pin "57") (pinfunction "VCC_57") (pintype "bidirectional"))
      (node (ref "U18") (pin "73") (pinfunction "VCCA_BR_73") (pintype "bidirectional"))
      (node (ref "U18") (pin "85") (pinfunction "VCC_85") (pintype "bidirectional"))
      (node (ref "U18") (pin "96") (pinfunction "VCC_96") (pintype "bidirectional"))
    )
    (net (code "137") (name "PWR_LED_24V") (class "Default")
      (node (ref "C4") (pin "2") (pinfunction "2_2") (pintype "bidirectional"))
      (node (ref "C5") (pin "2") (pinfunction "2_2") (pintype "bidirectional"))
      (node (ref "C6") (pin "P") (pinfunction "A_P") (pintype "bidirectional"))
      (node (ref "CN2") (pin "10") (pinfunction "10_10") (pintype "bidirectional"))
      (node (ref "CN2") (pin "8") (pinfunction "8_8") (pintype "bidirectional"))
      (node (ref "CN2") (pin "9") (pinfunction "9_9") (pintype "bidirectional"))
      (node (ref "Q1") (pin "5") (pinfunction "D_5") (pintype "bidirectional"))
      (node (ref "Q1") (pin "6") (pinfunction "D_6") (pintype "bidirectional"))
      (node (ref "Q1") (pin "7") (pinfunction "D_7") (pintype "bidirectional"))
      (node (ref "Q1") (pin "8") (pinfunction "D_8") (pintype "bidirectional"))
      (node (ref "Q1") (pin "PAD") (pinfunction "D_PAD") (pintype "bidirectional"))
      (node (ref "U1") (pin "3") (pinfunction "VIN_3") (pintype "bidirectional"))
    )
    (net (code "138") (name "PWR_SYS_3V3") (class "Default")
      (node (ref "C22") (pin "2") (pinfunction "2_2") (pintype "bidirectional"))
      (node (ref "C25") (pin "2") (pinfunction "2_2") (pintype "bidirectional"))
      (node (ref "C27") (pin "2") (pinfunction "2_2") (pintype "bidirectional"))
      (node (ref "C28") (pin "1") (pinfunction "1_1") (pintype "bidirectional"))
      (node (ref "C29") (pin "2") (pinfunction "2_2") (pintype "bidirectional"))
      (node (ref "C30") (pin "2") (pinfunction "2_2") (pintype "bidirectional"))
      (node (ref "C31") (pin "2") (pinfunction "2_2") (pintype "bidirectional"))
      (node (ref "C32") (pin "2") (pinfunction "2_2") (pintype "bidirectional"))
      (node (ref "C33") (pin "2") (pinfunction "2_2") (pintype "bidirectional"))
      (node (ref "C34") (pin "2") (pinfunction "2_2") (pintype "bidirectional"))
      (node (ref "C35") (pin "2") (pinfunction "2_2") (pintype "bidirectional"))
      (node (ref "C36") (pin "2") (pinfunction "2_2") (pintype "bidirectional"))
      (node (ref "C38") (pin "2") (pinfunction "2_2") (pintype "bidirectional"))
      (node (ref "C44") (pin "2") (pinfunction "2_2") (pintype "bidirectional"))
      (node (ref "C45") (pin "2") (pinfunction "2_2") (pintype "bidirectional"))
      (node (ref "C46") (pin "2") (pinfunction "2_2") (pintype "bidirectional"))
      (node (ref "C48") (pin "2") (pinfunction "2_2") (pintype "bidirectional"))
      (node (ref "C52") (pin "2") (pinfunction "2_2") (pintype "bidirectional"))
      (node (ref "C53") (pin "2") (pinfunction "2_2") (pintype "bidirectional"))
      (node (ref "C54") (pin "2") (pinfunction "2_2") (pintype "bidirectional"))
      (node (ref "C59") (pin "2") (pinfunction "2_2") (pintype "bidirectional"))
      (node (ref "C64") (pin "2") (pinfunction "2_2") (pintype "bidirectional"))
      (node (ref "CN4") (pin "1") (pinfunction "1_1") (pintype "bidirectional"))
      (node (ref "CN7") (pin "1") (pinfunction "1_1") (pintype "bidirectional"))
      (node (ref "L2") (pin "2") (pinfunction "2_2") (pintype "bidirectional"))
      (node (ref "OSC1") (pin "1") (pinfunction "~{ST}_1") (pintype "bidirectional"))
      (node (ref "OSC1") (pin "4") (pinfunction "VCC_4") (pintype "bidirectional"))
      (node (ref "R11") (pin "2") (pinfunction "2_2") (pintype "bidirectional"))
      (node (ref "R12") (pin "2") (pinfunction "2_2") (pintype "bidirectional"))
      (node (ref "R13") (pin "2") (pinfunction "2_2") (pintype "bidirectional"))
      (node (ref "R130") (pin "2") (pinfunction "2_2") (pintype "bidirectional"))
      (node (ref "R137") (pin "2") (pinfunction "2_2") (pintype "bidirectional"))
      (node (ref "R138") (pin "2") (pinfunction "2_2") (pintype "bidirectional"))
      (node (ref "R139") (pin "2") (pinfunction "2_2") (pintype "bidirectional"))
      (node (ref "R14") (pin "2") (pinfunction "2_2") (pintype "bidirectional"))
      (node (ref "R140") (pin "2") (pinfunction "2_2") (pintype "bidirectional"))
      (node (ref "R141") (pin "2") (pinfunction "2_2") (pintype "bidirectional"))
      (node (ref "R142") (pin "2") (pinfunction "2_2") (pintype "bidirectional"))
      (node (ref "R143") (pin "2") (pinfunction "2_2") (pintype "bidirectional"))
      (node (ref "R144") (pin "2") (pinfunction "2_2") (pintype "bidirectional"))
      (node (ref "R145") (pin "2") (pinfunction "2_2") (pintype "bidirectional"))
      (node (ref "R146") (pin "2") (pinfunction "2_2") (pintype "bidirectional"))
      (node (ref "R147") (pin "2") (pinfunction "2_2") (pintype "bidirectional"))
      (node (ref "R18") (pin "2") (pinfunction "2_2") (pintype "bidirectional"))
      (node (ref "R20") (pin "2") (pinfunction "2_2") (pintype "bidirectional"))
      (node (ref "R21") (pin "2") (pinfunction "2_2") (pintype "bidirectional"))
      (node (ref "R3") (pin "2") (pinfunction "2_2") (pintype "bidirectional"))
      (node (ref "R59") (pin "2") (pinfunction "2_2") (pintype "bidirectional"))
      (node (ref "R7") (pin "2") (pinfunction "2_2") (pintype "bidirectional"))
      (node (ref "R8") (pin "2") (pinfunction "2_2") (pintype "bidirectional"))
      (node (ref "R9") (pin "2") (pinfunction "2_2") (pintype "bidirectional"))
      (node (ref "U18") (pin "12") (pinfunction "VCCIO1C_1D_12") (pintype "bidirectional"))
      (node (ref "U18") (pin "122") (pinfunction "VCCIO3A_122") (pintype "bidirectional"))
      (node (ref "U18") (pin "143") (pinfunction "VCCIO1E_143") (pintype "bidirectional"))
      (node (ref "U18") (pin "21") (pinfunction "VCCIO1B_21") (pintype "bidirectional"))
      (node (ref "U18") (pin "23") (pinfunction "VCCIO1A_23") (pintype "bidirectional"))
      (node (ref "U18") (pin "51") (pinfunction "VCCIO4B_51") (pintype "bidirectional"))
      (node (ref "U18") (pin "52") (pinfunction "VCCIO4B_52") (pintype "bidirectional"))
      (node (ref "U18") (pin "62") (pinfunction "VCCIO4A_62") (pintype "bidirectional"))
      (node (ref "U18") (pin "63") (pinfunction "VCCIO4A_63") (pintype "bidirectional"))
      (node (ref "U18") (pin "88") (pinfunction "VCCIO3E_88") (pintype "bidirectional"))
      (node (ref "U18") (pin "91") (pinfunction "VCCIO3D_91") (pintype "bidirectional"))
      (node (ref "U18") (pin "95") (pinfunction "VCCIO3B_3C_95") (pintype "bidirectional"))
      (node (ref "U23") (pin "15") (pinfunction "VCCIO_15") (pintype "bidirectional"))
      (node (ref "U3") (pin "8") (pinfunction "V+_8") (pintype "bidirectional"))
      (node (ref "U4") (pin "8") (pinfunction "VCC_8") (pintype "bidirectional"))
      (node (ref "U5") (pin "5") (pinfunction "EN_5") (pintype "bidirectional"))
      (node (ref "U5") (pin "7") (pinfunction "VIN_7") (pintype "bidirectional"))
      (node (ref "U5") (pin "8") (pinfunction "VIN_8") (pintype "bidirectional"))
      (node (ref "U6") (pin "20") (pinfunction "VCCIO_20") (pintype "bidirectional"))
      (node (ref "U6") (pin "31") (pinfunction "VCCIO_31") (pintype "bidirectional"))
      (node (ref "U6") (pin "4") (pinfunction "VPHY_4") (pintype "bidirectional"))
      (node (ref "U6") (pin "42") (pinfunction "VCCIO_42") (pintype "bidirectional"))
      (node (ref "U6") (pin "50") (pinfunction "VREGIN_50") (pintype "bidirectional"))
      (node (ref "U6") (pin "56") (pinfunction "VCCIO_56") (pintype "bidirectional"))
      (node (ref "U6") (pin "9") (pinfunction "VPLL_9") (pintype "bidirectional"))
    )
    (net (code "139") (name "PWR_SYS_12V") (class "Default")
      (node (ref "C18") (pin "2") (pinfunction "2_2") (pintype "bidirectional"))
      (node (ref "C19") (pin "2") (pinfunction "2_2") (pintype "bidirectional"))
      (node (ref "C20") (pin "2") (pinfunction "2_2") (pintype "bidirectional"))
      (node (ref "C40") (pin "2") (pinfunction "2_2") (pintype "bidirectional"))
      (node (ref "C41") (pin "2") (pinfunction "2_2") (pintype "bidirectional"))
      (node (ref "C42") (pin "2") (pinfunction "2_2") (pintype "bidirectional"))
      (node (ref "C47") (pin "2") (pinfunction "2_2") (pintype "bidirectional"))
      (node (ref "C65") (pin "2") (pinfunction "2_2") (pintype "bidirectional"))
      (node (ref "C66") (pin "2") (pinfunction "2_2") (pintype "bidirectional"))
      (node (ref "C67") (pin "1") (pinfunction "A_1") (pintype "bidirectional"))
      (node (ref "C69") (pin "2") (pinfunction "2_2") (pintype "bidirectional"))
      (node (ref "L1") (pin "2") (pinfunction "2_2") (pintype "bidirectional"))
      (node (ref "R2") (pin "2") (pinfunction "2_2") (pintype "bidirectional"))
      (node (ref "U23") (pin "22") (pinfunction "VS_22") (pintype "bidirectional"))
      (node (ref "U23") (pin "28") (pinfunction "VS_28") (pintype "bidirectional"))
      (node (ref "U7") (pin "3") (pinfunction "VIN_3") (pintype "bidirectional"))
      (node (ref "U7") (pin "5") (pinfunction "EN_5") (pintype "bidirectional"))
    )
    (net (code "140") (name "PWR_USB_VBUS") (class "Default")
      (node (ref "C21") (pin "2") (pinfunction "2_2") (pintype "bidirectional"))
      (node (ref "FB3") (pin "2") (pinfunction "2_2") (pintype "bidirectional"))
      (node (ref "U2") (pin "5") (pinfunction "VBUS_5") (pintype "bidirectional"))
    )
    (net (code "141") (name "STP_CLK") (class "Default")
      (node (ref "U18") (pin "71") (pinfunction "GPIOB_CLKP0_71") (pintype "bidirectional"))
      (node (ref "U23") (pin "13") (pinfunction "CLK_13") (pintype "bidirectional"))
    )
    (net (code "142") (name "STP_DIA") (class "Default")
      (node (ref "U18") (pin "84") (pinfunction "GPIOR_135_CDI17_84") (pintype "bidirectional"))
      (node (ref "U23") (pin "11") (pinfunction "DIAG_11") (pintype "bidirectional"))
    )
    (net (code "143") (name "STP_DIR") (class "Default")
      (node (ref "U18") (pin "68") (pinfunction "GPIOB_RXN10_68") (pintype "bidirectional"))
      (node (ref "U23") (pin "19") (pinfunction "DIR_19") (pintype "bidirectional"))
    )
    (net (code "144") (name "STP_IDX") (class "Default")
      (node (ref "U18") (pin "72") (pinfunction "GPIOB_CLKN0_72") (pintype "bidirectional"))
      (node (ref "U23") (pin "12") (pinfunction "INDEX_12") (pintype "bidirectional"))
    )
    (net (code "145") (name "STP_MS1") (class "Default")
      (node (ref "U18") (pin "76") (pinfunction "GPIOR_155_76") (pintype "bidirectional"))
      (node (ref "U23") (pin "9") (pinfunction "MS1_9") (pintype "bidirectional"))
    )
    (net (code "146") (name "STP_MS2") (class "Default")
      (node (ref "U18") (pin "77") (pinfunction "GPIOR_154_77") (pintype "bidirectional"))
      (node (ref "U23") (pin "10") (pinfunction "MS2_10") (pintype "bidirectional"))
    )
    (net (code "147") (name "STP_MTR_A1") (class "Default")
      (node (ref "CN6") (pin "2") (pinfunction "2_2") (pintype "bidirectional"))
      (node (ref "U23") (pin "24") (pinfunction "OA1_24") (pintype "bidirectional"))
    )
    (net (code "148") (name "STP_MTR_A2") (class "Default")
      (node (ref "CN6") (pin "1") (pinfunction "1_1") (pintype "bidirectional"))
      (node (ref "U23") (pin "21") (pinfunction "OA2_21") (pintype "bidirectional"))
    )
    (net (code "149") (name "STP_MTR_B1") (class "Default")
      (node (ref "CN6") (pin "3") (pinfunction "3_3") (pintype "bidirectional"))
      (node (ref "U23") (pin "26") (pinfunction "OB1_26") (pintype "bidirectional"))
    )
    (net (code "150") (name "STP_MTR_B2") (class "Default")
      (node (ref "CN6") (pin "4") (pinfunction "4_4") (pintype "bidirectional"))
      (node (ref "U23") (pin "1") (pinfunction "OB2_1") (pintype "bidirectional"))
    )
    (net (code "151") (name "STP_NEN") (class "Default")
      (node (ref "U18") (pin "67") (pinfunction "GPIOB_RXP10_67") (pintype "bidirectional"))
      (node (ref "U23") (pin "2") (pinfunction "ENN_2") (pintype "bidirectional"))
    )
    (net (code "152") (name "STP_STP") (class "Default")
      (node (ref "U18") (pin "69") (pinfunction "GPIOB_RXN12_EXTFB0_69") (pintype "bidirectional"))
      (node (ref "U23") (pin "16") (pinfunction "STEP_16") (pintype "bidirectional"))
    )
    (net (code "153") (name "STP_UART_IO") (class "Default")
      (node (ref "U18") (pin "70") (pinfunction "GPIOB_RXP12_EXTFB0_70") (pintype "bidirectional"))
      (node (ref "U23") (pin "14") (pinfunction "PDN_UART_14") (pintype "bidirectional"))
    )
    (net (code "154") (name "TEMP_SEN_A") (class "Default")
      (node (ref "CN2") (pin "2") (pinfunction "2_2") (pintype "bidirectional"))
    )
    (net (code "155") (name "TEMP_SEN_B") (class "Default")
      (node (ref "CN2") (pin "1") (pinfunction "1_1") (pintype "bidirectional"))
    )
    (net (code "156") (name "USB_D_N") (class "Default")
      (node (ref "U2") (pin "6") (pinfunction "D+_OUT_6") (pintype "bidirectional"))
      (node (ref "U6") (pin "7") (pinfunction "D-_7") (pintype "bidirectional"))
    )
    (net (code "157") (name "USB_D_P") (class "Default")
      (node (ref "U2") (pin "4") (pinfunction "D-OUT_4") (pintype "bidirectional"))
      (node (ref "U6") (pin "8") (pinfunction "D+_8") (pintype "bidirectional"))
    )
    (net (code "158") (name "unconnected-(CN3-Pad1)") (class "Default")
      (node (ref "CN3") (pin "1") (pinfunction "1_1") (pintype "bidirectional"))
    )
    (net (code "159") (name "unconnected-(CN3-Pad2)") (class "Default")
      (node (ref "CN3") (pin "2") (pinfunction "2_2") (pintype "bidirectional"))
    )
    (net (code "160") (name "unconnected-(CN3-Pad3)") (class "Default")
      (node (ref "CN3") (pin "3") (pinfunction "3_3") (pintype "bidirectional"))
    )
    (net (code "161") (name "unconnected-(CN3-Pad4)") (class "Default")
      (node (ref "CN3") (pin "4") (pinfunction "4_4") (pintype "bidirectional"))
    )
    (net (code "162") (name "unconnected-(CN3-Pad5)") (class "Default")
      (node (ref "CN3") (pin "5") (pinfunction "5_5") (pintype "bidirectional"))
    )
    (net (code "163") (name "unconnected-(CN3-Pad6)") (class "Default")
      (node (ref "CN3") (pin "6") (pinfunction "6_6") (pintype "bidirectional"))
    )
    (net (code "164") (name "unconnected-(CN3-Pad7)") (class "Default")
      (node (ref "CN3") (pin "7") (pinfunction "7_7") (pintype "bidirectional"))
    )
    (net (code "165") (name "unconnected-(CN3-Pad8)") (class "Default")
      (node (ref "CN3") (pin "8") (pinfunction "8_8") (pintype "bidirectional"))
    )
    (net (code "166") (name "unconnected-(CN3-Pad9)") (class "Default")
      (node (ref "CN3") (pin "9") (pinfunction "9_9") (pintype "bidirectional"))
    )
    (net (code "167") (name "unconnected-(CN3-Pad10)") (class "Default")
      (node (ref "CN3") (pin "10") (pinfunction "10_10") (pintype "bidirectional"))
    )
    (net (code "168") (name "unconnected-(CN3-Pad11)") (class "Default")
      (node (ref "CN3") (pin "11") (pinfunction "11_11") (pintype "bidirectional"))
    )
    (net (code "169") (name "unconnected-(CN3-Pad12)") (class "Default")
      (node (ref "CN3") (pin "12") (pinfunction "12_12") (pintype "bidirectional"))
    )
    (net (code "170") (name "unconnected-(CN3-Pad13)") (class "Default")
      (node (ref "CN3") (pin "13") (pinfunction "13_13") (pintype "bidirectional"))
    )
    (net (code "171") (name "unconnected-(CN3-Pad14)") (class "Default")
      (node (ref "CN3") (pin "14") (pinfunction "14_14") (pintype "bidirectional"))
    )
    (net (code "172") (name "unconnected-(CN3-Pad15)") (class "Default")
      (node (ref "CN3") (pin "15") (pinfunction "15_15") (pintype "bidirectional"))
    )
    (net (code "173") (name "unconnected-(CN5-SENSE-Pad2)") (class "Default")
      (node (ref "CN5") (pin "2") (pinfunction "SENSE_2") (pintype "bidirectional"))
    )
    (net (code "174") (name "unconnected-(CN7-Pad6)") (class "Default")
      (node (ref "CN7") (pin "6") (pinfunction "6_6") (pintype "bidirectional"))
    )
    (net (code "175") (name "unconnected-(CN7-Pad7)") (class "Default")
      (node (ref "CN7") (pin "7") (pinfunction "7_7") (pintype "bidirectional"))
    )
    (net (code "176") (name "unconnected-(SW1A-2-Pad1)") (class "Default")
      (node (ref "SW1") (pin "1") (pinfunction "2_1") (pintype "bidirectional"))
    )
    (net (code "177") (name "unconnected-(U1-EN-Pad5)") (class "Default")
      (node (ref "U1") (pin "5") (pinfunction "EN_5") (pintype "bidirectional"))
    )
    (net (code "178") (name "unconnected-(U6-ACBUS7-Pad34)") (class "Default")
      (node (ref "U6") (pin "34") (pinfunction "ACBUS7_34") (pintype "bidirectional"))
    )
    (net (code "179") (name "unconnected-(U6-BCBUS1-Pad52)") (class "Default")
      (node (ref "U6") (pin "52") (pinfunction "BCBUS1_52") (pintype "bidirectional"))
    )
    (net (code "180") (name "unconnected-(U6-BCBUS2-Pad53)") (class "Default")
      (node (ref "U6") (pin "53") (pinfunction "BCBUS2_53") (pintype "bidirectional"))
    )
    (net (code "181") (name "unconnected-(U6-BCBUS5-Pad57)") (class "Default")
      (node (ref "U6") (pin "57") (pinfunction "BCBUS5_57") (pintype "bidirectional"))
    )
    (net (code "182") (name "unconnected-(U6-BCBUS6-Pad58)") (class "Default")
      (node (ref "U6") (pin "58") (pinfunction "BCBUS6_58") (pintype "bidirectional"))
    )
    (net (code "183") (name "unconnected-(U18-GPIOL_05_CSO-Pad33)") (class "Default")
      (node (ref "U18") (pin "33") (pinfunction "GPIOL_05_CSO_33") (pintype "bidirectional"))
    )
    (net (code "184") (name "unconnected-(U23-VREF-Pad17)") (class "Default")
      (node (ref "U23") (pin "17") (pinfunction "VREF_17") (pintype "bidirectional"))
    )
  )
)
